# f407_board.net
KiCad netlist of a schematic drawn in Altium Designer
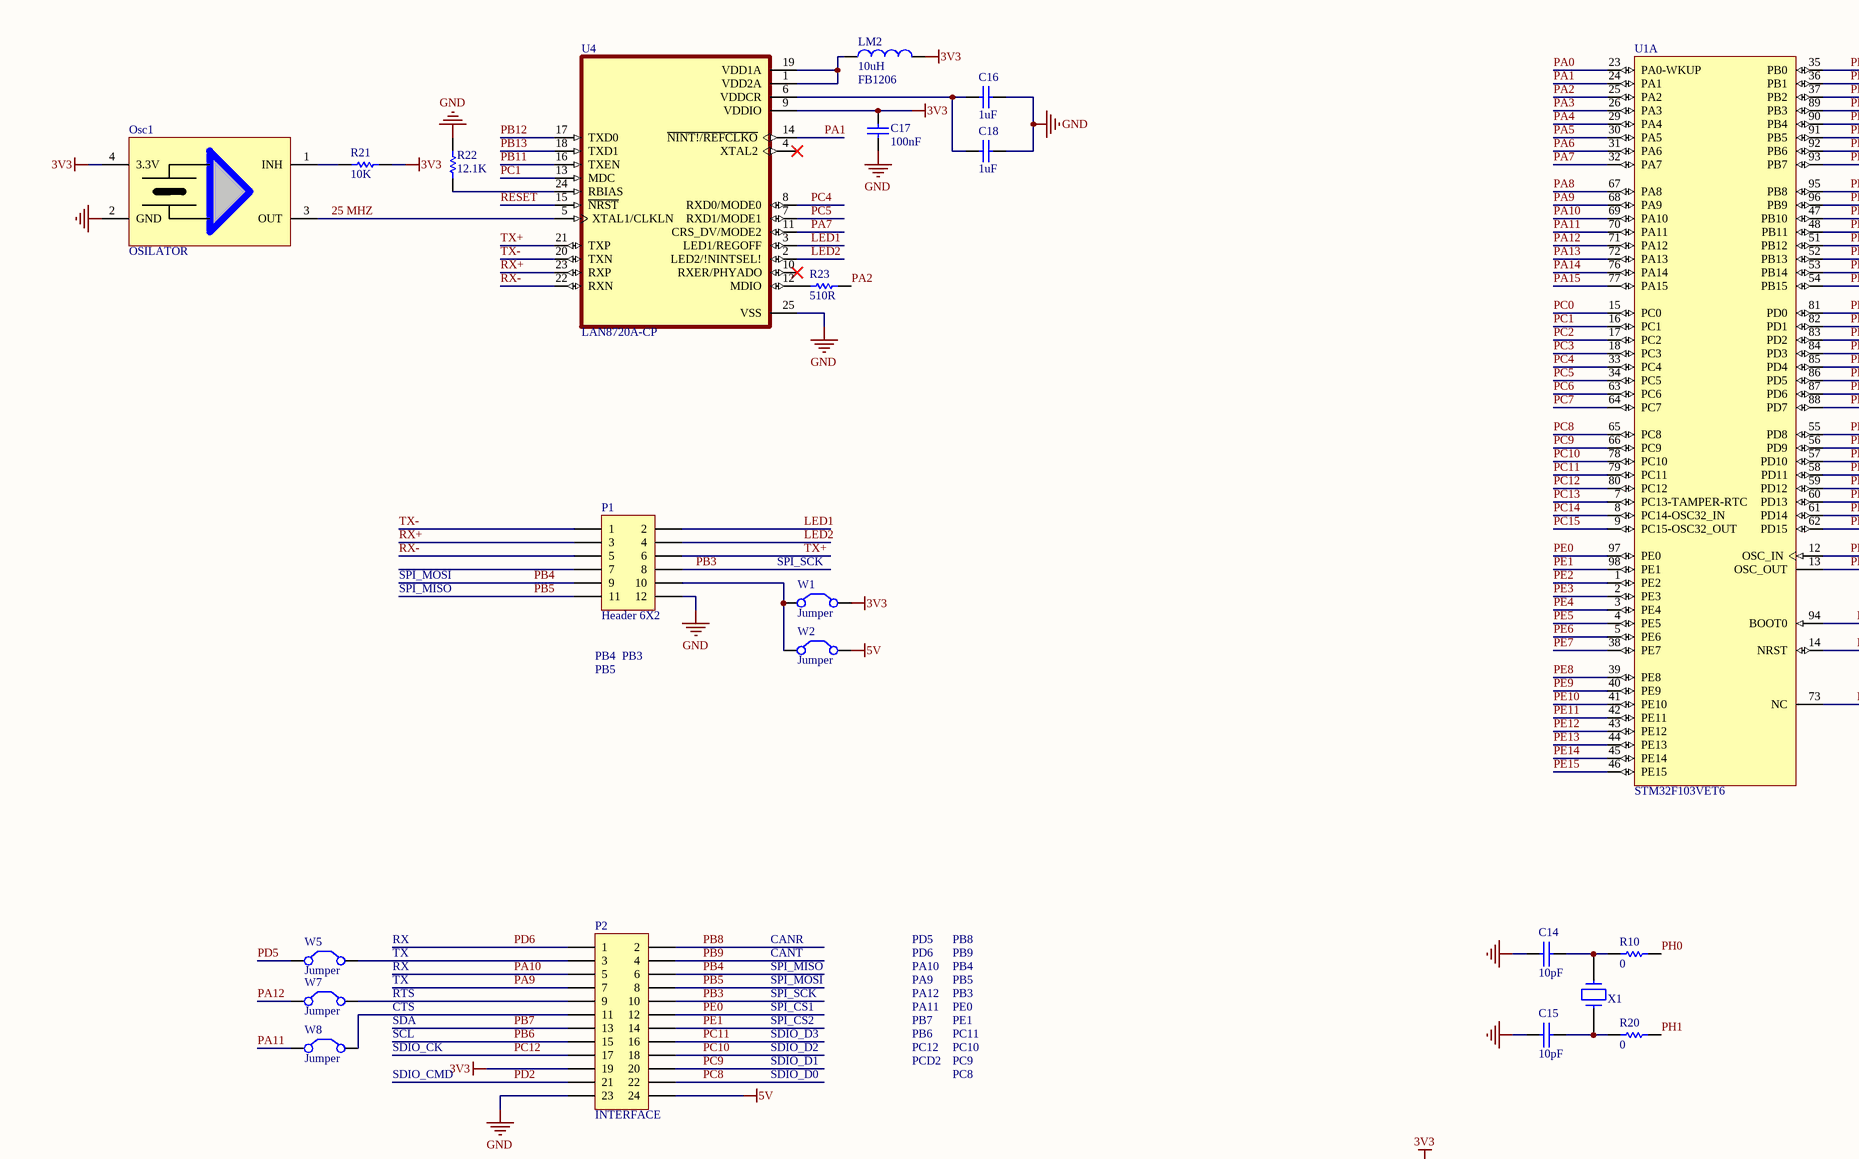
[diagram p0: f407 board.SchDoc, top left]
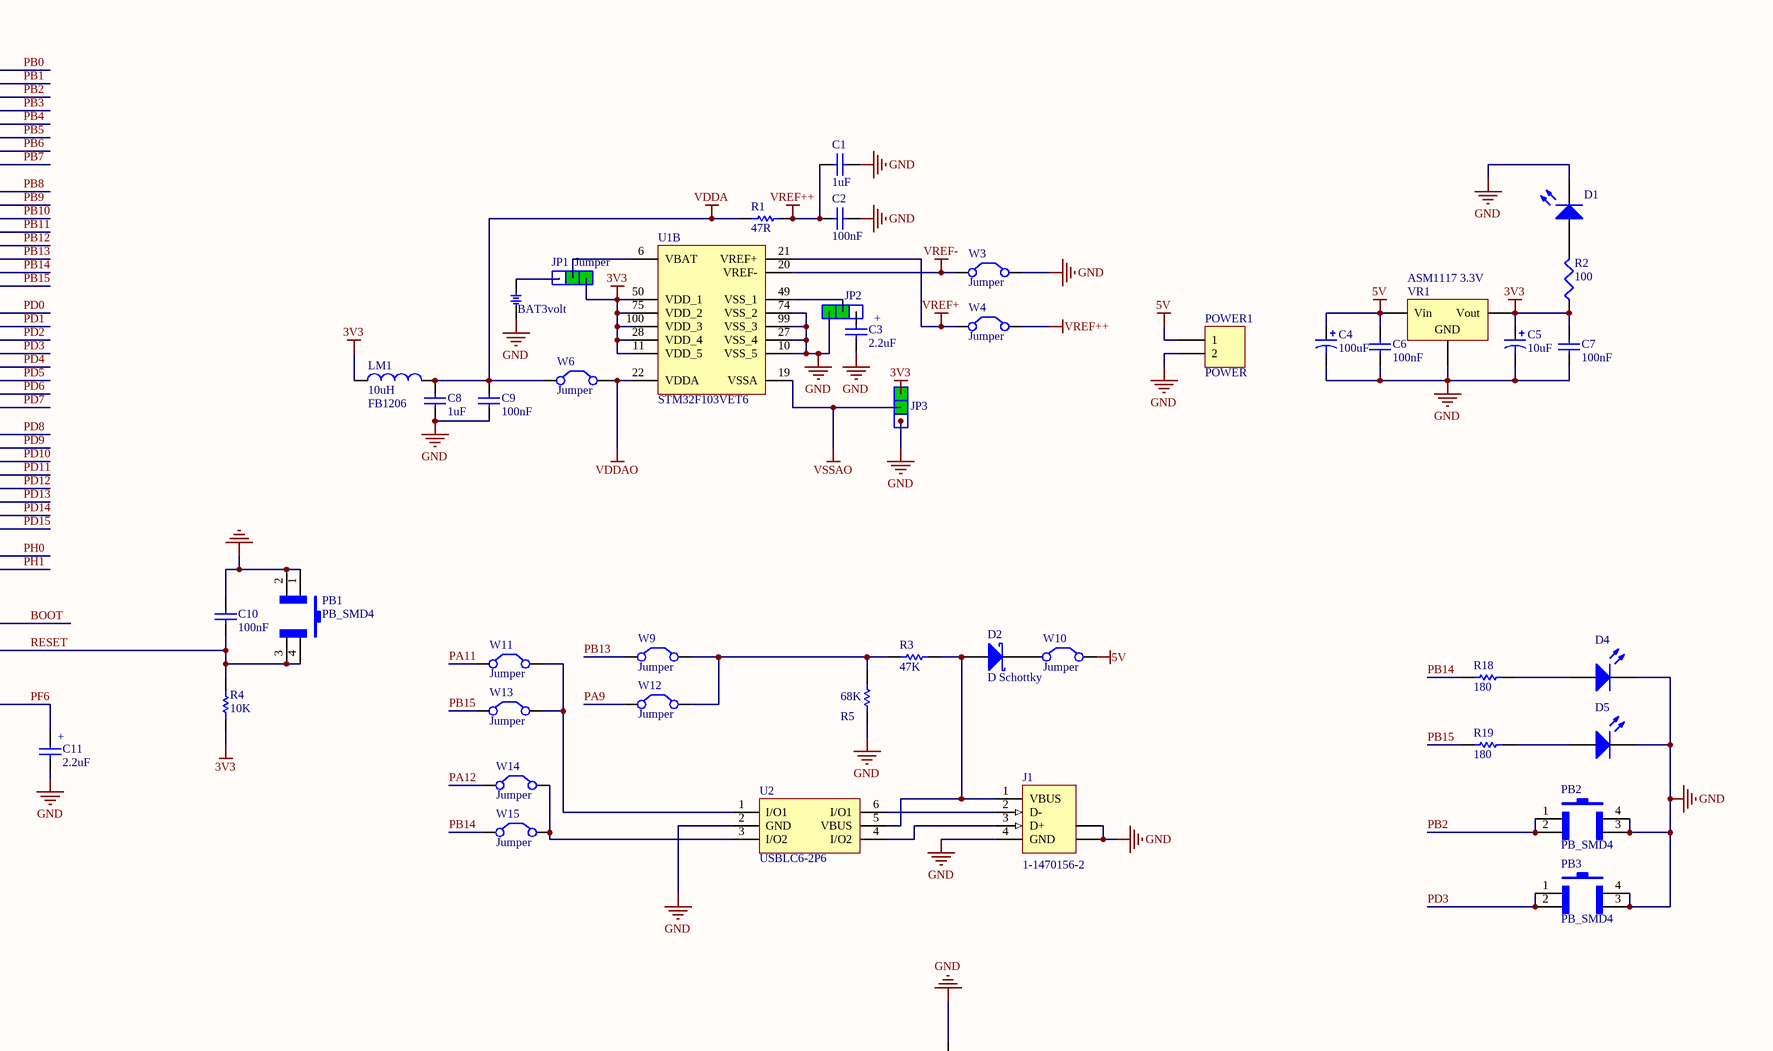
[diagram p1: f407 board.SchDoc, top right]
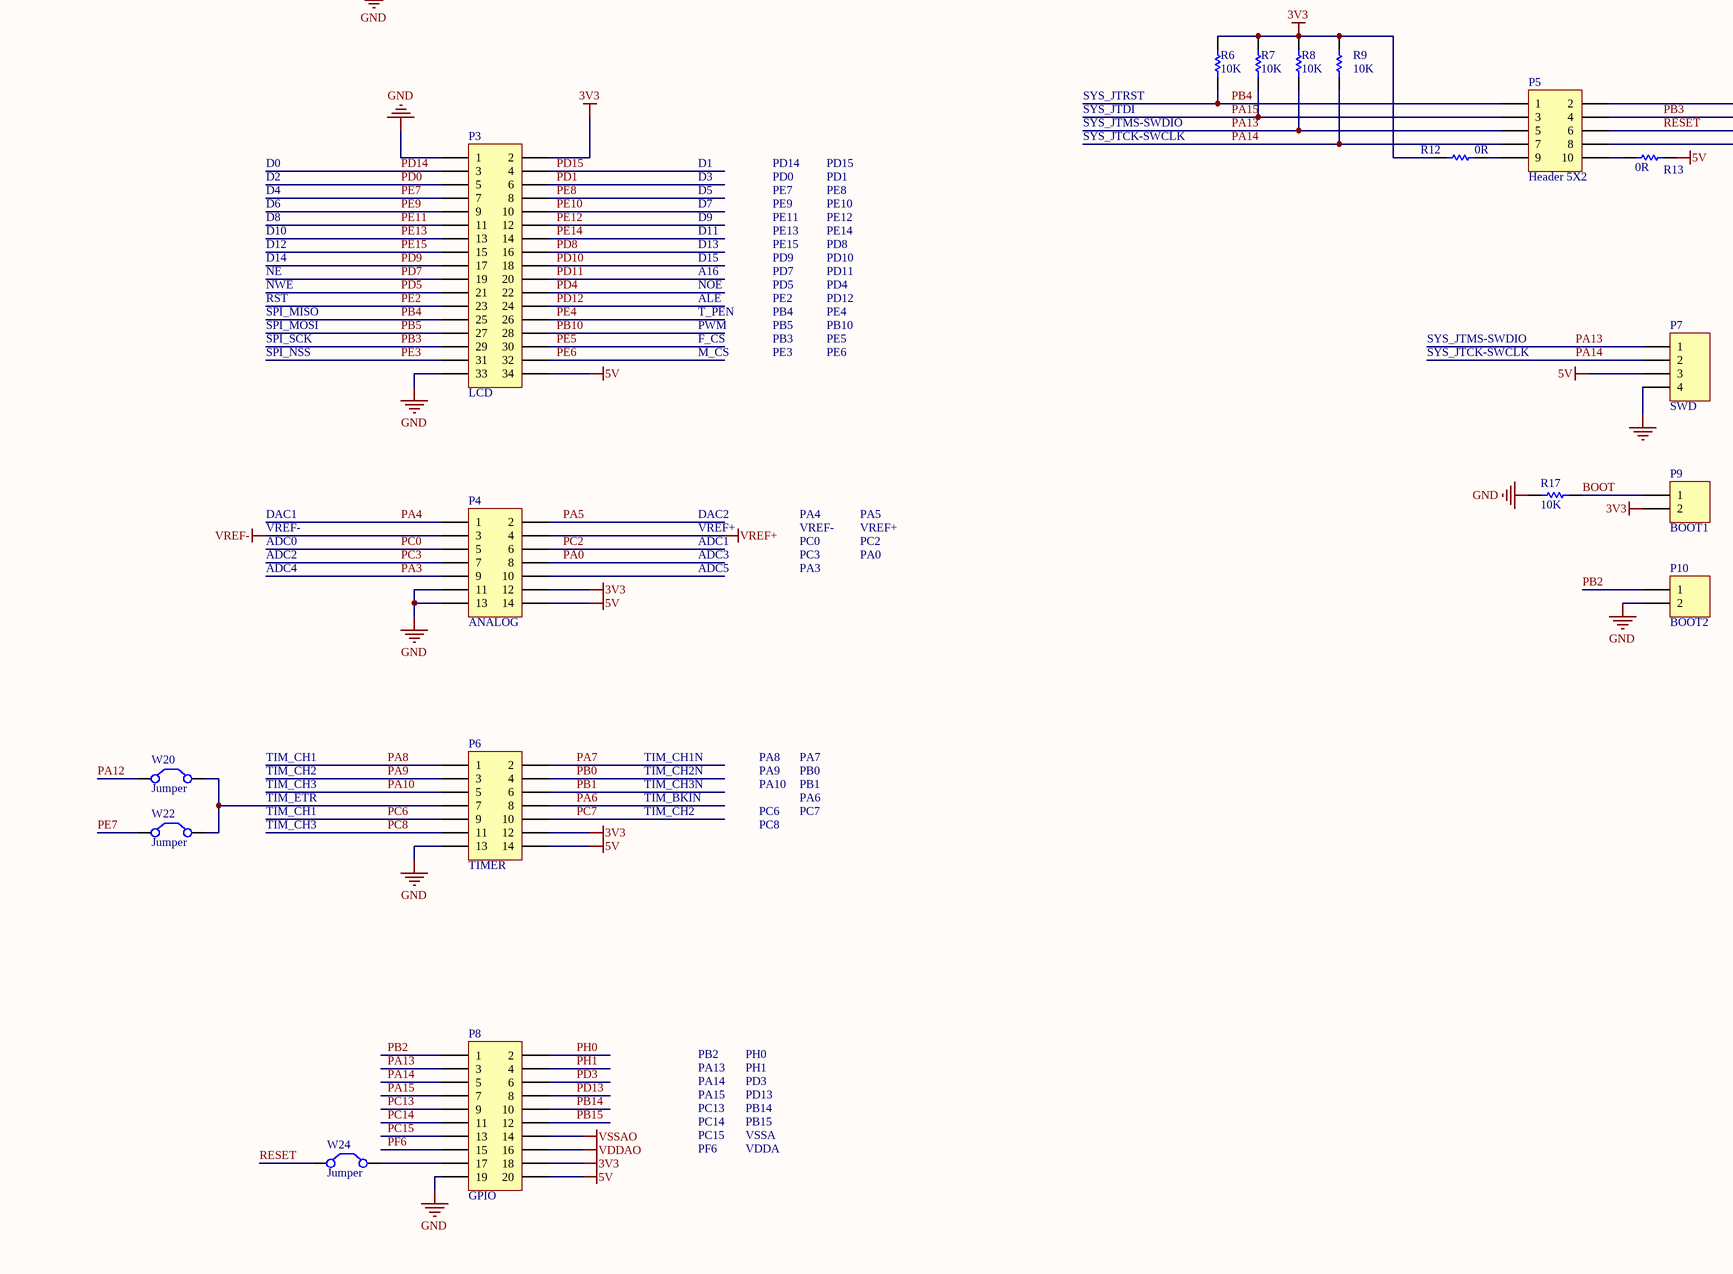
[diagram p2: f407 board.SchDoc, bottom left]
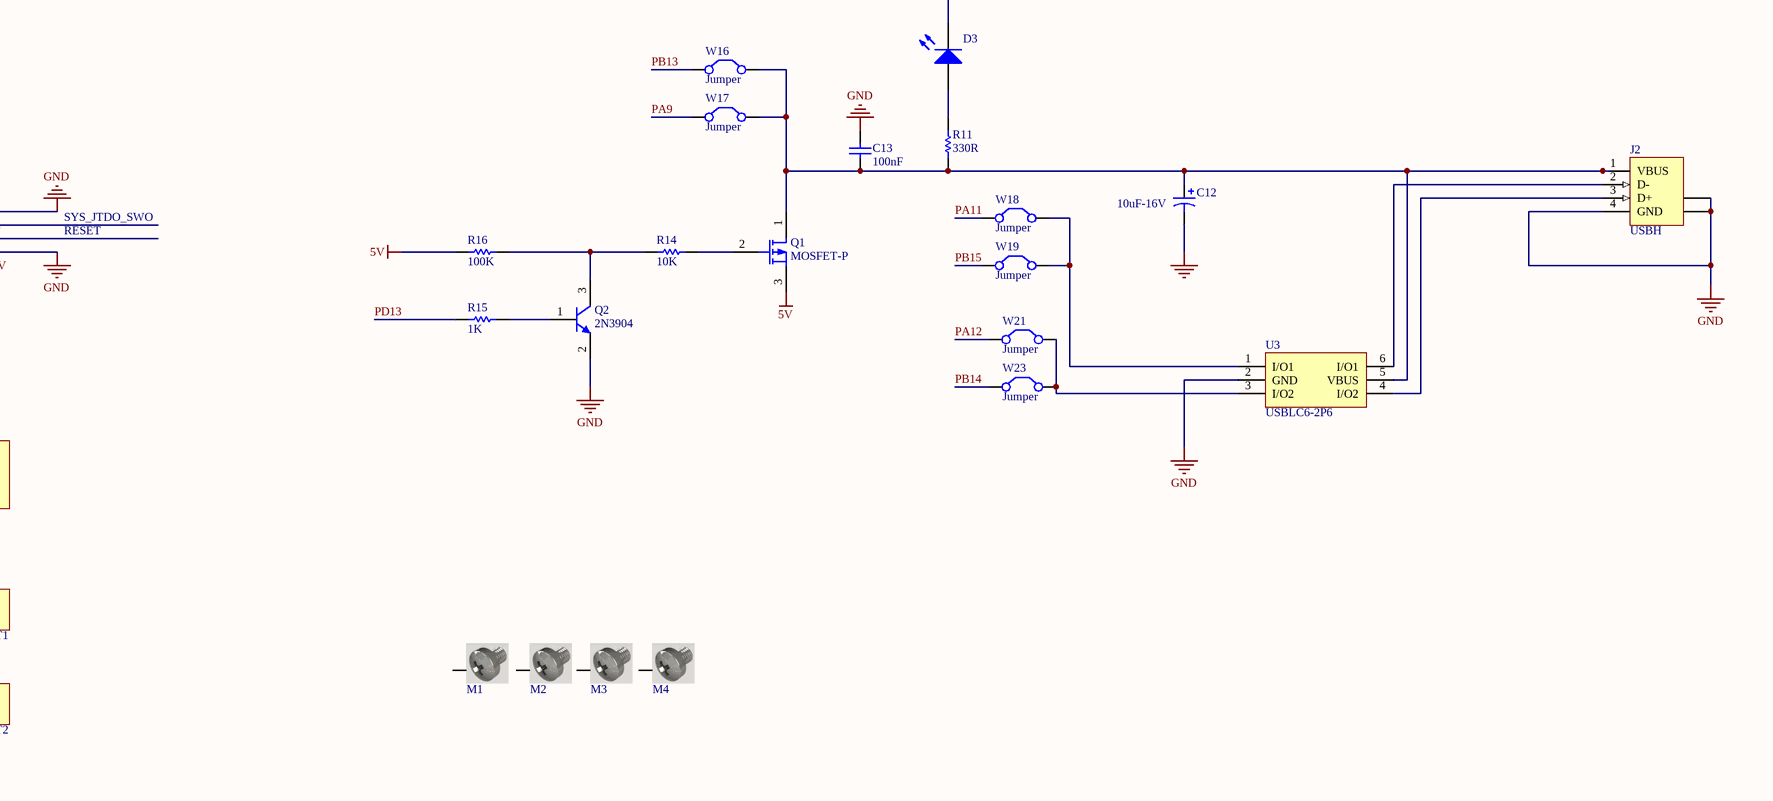
[diagram p3: f407 board.SchDoc, bottom right]

(export (version "E")
  (design (tool "Eeschema 10.0.6"))
  (components
    (comp (ref "BT1")
      (value "BAT3volt")
      (footprint "BTH1220")
      (description "BATTERY HOLDER, CR1220/CR2032")
      (libsource (lib "battery") (part "BATH_CR1220_CR2032"))
    )
    (comp (ref "C1")
      (value "1uF")
      (footprint "0805")
      (description "CAP 1206")
      (fields (field (name "DESIGNER") "Abbas Basereh"))
      (libsource (lib "2017AbbasBasereh9365731239 -ver1") (part "CAP SMD 1206"))
    )
    (comp (ref "C2")
      (value "100nF")
      (footprint "0805")
      (description "CAP 1206")
      (fields (field (name "DESIGNER") "Abbas Basereh"))
      (libsource (lib "2017AbbasBasereh9365731239 -ver1") (part "CAP SMD 1206"))
    )
    (comp (ref "C3")
      (value "2.2uF")
      (footprint "0805")
      (description "CAP 1206")
      (fields (field (name "DESIGNER") "Abbas Basereh"))
      (libsource (lib "2017AbbasBasereh9365731239 -ver1") (part "CAP SMD 1206"))
    )
    (comp (ref "C4")
      (value "100uF")
      (footprint "CAP470")
      (description "Polarized Capacitor (Radial)")
      (fields (field (name "Comment") "100uf") (field (name "PUBLISHER") "Altium Limited"))
      (libsource (lib "Miscellaneous Devices") (part "Cap Pol1"))
    )
    (comp (ref "C5")
      (value "10uF")
      (footprint "CAP10")
      (description "Polarized Capacitor (Radial)")
      (fields (field (name "Comment") "10uf") (field (name "PUBLISHER") "Altium Limited"))
      (libsource (lib "Miscellaneous Devices") (part "Cap Pol1"))
    )
    (comp (ref "C6")
      (value "100nF")
      (footprint "0805")
      (description "Capacitor (Semiconductor SIM Model)")
      (fields (field (name "PUBLISHER") "Altium Limited"))
      (libsource (lib "Miscellaneous Devices") (part "Cap Semi"))
    )
    (comp (ref "C7")
      (value "100nF")
      (footprint "0805")
      (description "Capacitor (Semiconductor SIM Model)")
      (fields (field (name "PUBLISHER") "Altium Limited"))
      (libsource (lib "Miscellaneous Devices") (part "Cap Semi"))
    )
    (comp (ref "C8")
      (value "1uF")
      (footprint "0805")
      (description "CAP 1206")
      (fields (field (name "DESIGNER") "Abbas Basereh"))
      (libsource (lib "2017AbbasBasereh9365731239 -ver1") (part "CAP SMD 1206"))
    )
    (comp (ref "C9")
      (value "100nF")
      (footprint "0805")
      (description "CAP 1206")
      (fields (field (name "DESIGNER") "Abbas Basereh"))
      (libsource (lib "2017AbbasBasereh9365731239 -ver1") (part "CAP SMD 1206"))
    )
    (comp (ref "C10")
      (value "100nF")
      (footprint "0805")
      (description "Capacitor")
      (fields (field (name "PUBLISHER") "Altium Limited"))
      (libsource (lib "Miscellaneous Devices") (part "CAP"))
    )
    (comp (ref "C11")
      (value "2.2uF")
      (footprint "0805")
      (description "CAP 1206")
      (fields (field (name "DESIGNER") "Abbas Basereh"))
      (libsource (lib "2017AbbasBasereh9365731239 -ver1") (part "CAP SMD 1206"))
    )
    (comp (ref "C12")
      (value "10uF-16V")
      (footprint "cap10")
      (description "Polarized Capacitor")
      (libsource (lib "mahdidadashi") (part "3-CAP-POL"))
    )
    (comp (ref "C13")
      (value "100nF")
      (footprint "0805")
      (description "Capacitor (Semiconductor SIM Model)")
      (fields (field (name "Comment") "10uf") (field (name "PUBLISHER") "Altium Limited"))
      (libsource (lib "Miscellaneous Devices") (part "Cap Semi"))
    )
    (comp (ref "C14")
      (value "10pF")
      (footprint "0805")
      (description "Capacitor")
      (libsource (lib "*") (part "CAP"))
    )
    (comp (ref "C15")
      (value "10pF")
      (footprint "0805")
      (description "Capacitor")
      (libsource (lib "*") (part "CAP"))
    )
    (comp (ref "C16")
      (value "1uF")
      (footprint "0805")
      (description "CAP 1206")
      (fields (field (name "DESIGNER") "Abbas Basereh"))
      (libsource (lib "2017AbbasBasereh9365731239 -ver1") (part "CAP SMD 1206"))
    )
    (comp (ref "C17")
      (value "100nF")
      (footprint "0805")
      (description "CAP 1206")
      (fields (field (name "DESIGNER") "Abbas Basereh"))
      (libsource (lib "2017AbbasBasereh9365731239 -ver1") (part "CAP SMD 1206"))
    )
    (comp (ref "C18")
      (value "1uF")
      (footprint "0805")
      (description "CAP 1206")
      (fields (field (name "DESIGNER") "Abbas Basereh"))
      (libsource (lib "2017AbbasBasereh9365731239 -ver1") (part "CAP SMD 1206"))
    )
    (comp (ref "D1")
      (value "LED0")
      (footprint "LED_0805")
      (description "Typical INFRARED GaAs LED")
      (fields (field (name "PUBLISHER") "Altium Limited"))
      (libsource (lib "Miscellaneous Devices") (part "LED0"))
    )
    (comp (ref "D2")
      (value "D Schottky")
      (footprint "SOD80, LL-34")
      (description "Schottky Diode")
      (fields (field (name "PUBLISHER") "Altium Limited"))
      (libsource (lib "Miscellaneous Devices") (part "D Schottky"))
    )
    (comp (ref "D3")
      (value "LED0")
      (footprint "LED_0805")
      (description "Typical INFRARED GaAs LED")
      (fields (field (name "PUBLISHER") "Altium Limited"))
      (libsource (lib "Miscellaneous Devices") (part "LED0"))
    )
    (comp (ref "D4")
      (value "LED0")
      (footprint "LED_0805")
      (description "Typical INFRARED GaAs LED")
      (fields (field (name "PUBLISHER") "Altium Limited"))
      (libsource (lib "Miscellaneous Devices") (part "LED0"))
    )
    (comp (ref "D5")
      (value "LED0")
      (footprint "LED_0805")
      (description "Typical INFRARED GaAs LED")
      (fields (field (name "PUBLISHER") "Altium Limited"))
      (libsource (lib "Miscellaneous Devices") (part "LED0"))
    )
    (comp (ref "J1")
      (value "1-1470156-2")
      (footprint "440247")
      (description "USB 1.1, Right Angle, Thru-Hole, B Type, Receptacle, 4 Position, Black")
      (fields (field (name "PUBLISHER") "Altium Limited"))
      (libsource (lib "AMP Serial Bus USB") (part "1-1470156-2"))
    )
    (comp (ref "J2")
      (value "USBH")
      (footprint "787761")
      (description "USB 1.1, Right Angle, Thru-Hole, A Type, Receptacle, 4 Position, Natural")
      (fields (field (name "PUBLISHER") "Altium Limited"))
      (libsource (lib "AMP Serial Bus USB") (part "787761-3"))
    )
    (comp (ref "JP1")
      (value "Jumper")
      (footprint "JT3")
      (description "Jumper Selector")
      (libsource (lib "Electrovolt Lib") (part "Jumper Selector"))
    )
    (comp (ref "JP2")
      (value "Jumper")
      (footprint "JT3")
      (description "Jumper Selector")
      (libsource (lib "") (part "Jumper Selector_1"))
    )
    (comp (ref "JP3")
      (value "Jumper")
      (footprint "JT3")
      (description "Jumper Selector")
      (libsource (lib "") (part "Jumper Selector_2"))
    )
    (comp (ref "LM1")
      (value "10uH")
      (footprint "0805")
      (description "Inductor")
      (fields (field (name "ALTIUM_VALUE") "FB1206") (field (name "PUBLISHER") "Altium Limited"))
      (libsource (lib "2017AbbasBasereh9365731239 -ver1") (part "L SMA 0.25W"))
    )
    (comp (ref "LM2")
      (value "10uH")
      (footprint "0805")
      (description "Inductor")
      (fields (field (name "ALTIUM_VALUE") "FB1206") (field (name "PUBLISHER") "Altium Limited"))
      (libsource (lib "2017AbbasBasereh9365731239 -ver1") (part "L SMA 0.25W"))
    )
    (comp (ref "M1")
      (value "Screw3mm")
      (footprint "Board Screw 3mm")
      (description "Board Screw With Spacer 3mm")
      (fields (field (name "DESIGNER") "Abbas Basereh"))
      (libsource (lib "2017AbbasBasereh9365731239 -ver1") (part "Board Screw 3mm"))
    )
    (comp (ref "M2")
      (value "Screw3mm")
      (footprint "Board Screw 3mm")
      (description "Board Screw With Spacer 3mm")
      (fields (field (name "DESIGNER") "Abbas Basereh"))
      (libsource (lib "2017AbbasBasereh9365731239 -ver1") (part "Board Screw 3mm"))
    )
    (comp (ref "M3")
      (value "Screw3mm")
      (footprint "Board Screw 3mm")
      (description "Board Screw With Spacer 3mm")
      (fields (field (name "DESIGNER") "Abbas Basereh"))
      (libsource (lib "2017AbbasBasereh9365731239 -ver1") (part "Board Screw 3mm"))
    )
    (comp (ref "M4")
      (value "Screw3mm")
      (footprint "Board Screw 3mm")
      (description "Board Screw With Spacer 3mm")
      (fields (field (name "DESIGNER") "Abbas Basereh"))
      (libsource (lib "2017AbbasBasereh9365731239 -ver1") (part "Board Screw 3mm"))
    )
    (comp (ref "Osc1")
      (value "OSILATOR")
      (footprint "XTAL_5X7")
      (libsource (lib "New Lib") (part "OSILATOR"))
    )
    (comp (ref "P1")
      (value "Header 6X2")
      (footprint "HDR2X6")
      (description "Header, 6-Pin, Dual row")
      (fields (field (name "PUBLISHER") "Altium Limited"))
      (libsource (lib "Miscellaneous Connectors") (part "Header 6X2"))
    )
    (comp (ref "P2")
      (value "INTERFACE")
      (footprint "HDR2X12")
      (description "Header, 12-Pin, Dual row")
      (fields (field (name "PUBLISHER") "Altium Limited"))
      (libsource (lib "Miscellaneous Connectors") (part "Header 12X2"))
    )
    (comp (ref "P3")
      (value "LCD")
      (footprint "HDR2X17")
      (description "Header, 17-Pin, Dual row")
      (fields (field (name "PUBLISHER") "Altium Limited"))
      (libsource (lib "Miscellaneous Connectors") (part "Header 17X2"))
    )
    (comp (ref "P4")
      (value "ANALOG")
      (footprint "HDR2X7")
      (description "Header, 7-Pin, Dual row")
      (fields (field (name "PUBLISHER") "Altium Limited"))
      (libsource (lib "Miscellaneous Connectors") (part "Header 7X2"))
    )
    (comp (ref "P5")
      (value "Header 5X2")
      (footprint "HDR2X5")
      (description "Header, 5-Pin, Dual row")
      (fields (field (name "PUBLISHER") "Altium Limited"))
      (libsource (lib "Miscellaneous Connectors") (part "Header 5X2"))
    )
    (comp (ref "P6")
      (value "TIMER")
      (footprint "HDR2X7")
      (description "Header, 7-Pin, Dual row")
      (fields (field (name "PUBLISHER") "Altium Limited"))
      (libsource (lib "Miscellaneous Connectors") (part "Header 7X2"))
    )
    (comp (ref "P7")
      (value "SWD")
      (footprint "HDR1X4")
      (description "Header, 4-Pin")
      (fields (field (name "PUBLISHER") "Altium Limited"))
      (libsource (lib "Miscellaneous Connectors") (part "Header 4"))
    )
    (comp (ref "P8")
      (value "GPIO")
      (footprint "HDR2X10")
      (description "Header, 10-Pin, Dual row")
      (fields (field (name "PUBLISHER") "Altium Limited"))
      (libsource (lib "Miscellaneous Connectors") (part "Header 10X2"))
    )
    (comp (ref "P9")
      (value "BOOT1")
      (footprint "HDR1X2")
      (description "Header, 2-Pin")
      (fields (field (name "PUBLISHER") "Altium Limited"))
      (libsource (lib "Miscellaneous Connectors") (part "Header 2"))
    )
    (comp (ref "P10")
      (value "BOOT2")
      (footprint "HDR1X2")
      (description "Header, 2-Pin")
      (fields (field (name "PUBLISHER") "Altium Limited"))
      (libsource (lib "Miscellaneous Connectors") (part "Header 2"))
    )
    (comp (ref "PB1")
      (value "PB_SMD4")
      (footprint "PB_SMD4")
      (fields (field (name "PART_NUMBER") "SW-PB-AX-SMD4"))
      (libsource (lib "SCHLib") (part "PB_SMD4"))
    )
    (comp (ref "PB2")
      (value "PB_SMD4")
      (footprint "PB_SMD4")
      (fields (field (name "PART_NUMBER") "SW-PB-AX-SMD4"))
      (libsource (lib "") (part "PB_SMD4_1"))
    )
    (comp (ref "PB3")
      (value "PB_SMD4")
      (footprint "PB_SMD4")
      (fields (field (name "PART_NUMBER") "SW-PB-AX-SMD4"))
      (libsource (lib "") (part "PB_SMD4_1"))
    )
    (comp (ref "POWER1")
      (value "POWER")
      (footprint "power jack")
      (description "Header, 2-Pin, Right Angle")
      (fields (field (name "PUBLISHER") "Altium Limited"))
      (libsource (lib "Miscellaneous Connectors") (part "Header 2H"))
    )
    (comp (ref "Q1")
      (value "MOSFET-P")
      (footprint "SUPER SOT_3")
      (description "P-Channel MOSFET")
      (fields (field (name "PUBLISHER") "Altium Limited"))
      (libsource (lib "Miscellaneous Devices") (part "MOSFET-P"))
    )
    (comp (ref "Q2")
      (value "2N3904")
      (footprint "SOT-23")
      (description "NPN General Purpose Amplifier")
      (fields (field (name "PUBLISHER") "Altium Limited"))
      (libsource (lib "Miscellaneous Devices") (part "2N3904"))
    )
    (comp (ref "R1")
      (value "47R")
      (footprint "0805")
      (description "RES 1206")
      (fields (field (name "DESIGNER") "Abbas Basereh"))
      (libsource (lib "2017AbbasBasereh9365731239 -ver1") (part "RES 1206 0.25W"))
    )
    (comp (ref "R2")
      (value "100")
      (footprint "0805")
      (description "Resistor")
      (fields (field (name "PUBLISHER") "Altium Limited"))
      (libsource (lib "Miscellaneous Devices") (part "Res3"))
    )
    (comp (ref "R3")
      (value "47K")
      (footprint "0805")
      (description "Resistor")
      (fields (field (name "PUBLISHER") "Altium Limited"))
      (libsource (lib "") (part "Res1_1"))
    )
    (comp (ref "R4")
      (value "10K")
      (footprint "0805")
      (description "Resistor")
      (fields (field (name "PUBLISHER") "Altium Limited"))
      (libsource (lib "Miscellaneous Devices") (part "res1"))
    )
    (comp (ref "R5")
      (value "68K")
      (footprint "0805")
      (description "Resistor")
      (fields (field (name "PUBLISHER") "Altium Limited"))
      (libsource (lib "") (part "Res1_1"))
    )
    (comp (ref "R6")
      (value "10K")
      (footprint "0805")
      (description "Resistor")
      (fields (field (name "PUBLISHER") "Altium Limited"))
      (libsource (lib "Miscellaneous Devices") (part "Res1"))
    )
    (comp (ref "R7")
      (value "10K")
      (footprint "0805")
      (description "Resistor")
      (fields (field (name "PUBLISHER") "Altium Limited"))
      (libsource (lib "Miscellaneous Devices") (part "Res1"))
    )
    (comp (ref "R8")
      (value "10K")
      (footprint "0805")
      (description "Resistor")
      (fields (field (name "PUBLISHER") "Altium Limited"))
      (libsource (lib "Miscellaneous Devices") (part "Res1"))
    )
    (comp (ref "R9")
      (value "10K")
      (footprint "0805")
      (description "Resistor")
      (fields (field (name "PUBLISHER") "Altium Limited"))
      (libsource (lib "Miscellaneous Devices") (part "Res1"))
    )
    (comp (ref "R10")
      (value "0")
      (footprint "0805")
      (description "Resistor")
      (fields (field (name "PUBLISHER") "Altium Limited"))
      (libsource (lib "Miscellaneous Devices") (part "Res1"))
    )
    (comp (ref "R11")
      (value "330R")
      (footprint "0805")
      (description "Resistor")
      (fields (field (name "PUBLISHER") "Altium Limited"))
      (libsource (lib "") (part "Res1_1"))
    )
    (comp (ref "R12")
      (value "0R")
      (footprint "0805")
      (description "Resistor")
      (fields (field (name "PUBLISHER") "Altium Limited"))
      (libsource (lib "Miscellaneous Devices") (part "Res1"))
    )
    (comp (ref "R13")
      (value "0R")
      (footprint "0805")
      (description "Resistor")
      (fields (field (name "PUBLISHER") "Altium Limited"))
      (libsource (lib "Miscellaneous Devices") (part "Res1"))
    )
    (comp (ref "R14")
      (value "10K")
      (footprint "0805")
      (description "Resistor")
      (fields (field (name "PUBLISHER") "Altium Limited"))
      (libsource (lib "") (part "Res1_1"))
    )
    (comp (ref "R15")
      (value "1K")
      (footprint "0805")
      (description "Resistor")
      (fields (field (name "PUBLISHER") "Altium Limited"))
      (libsource (lib "") (part "Res1_1"))
    )
    (comp (ref "R16")
      (value "100K")
      (footprint "0805")
      (description "Resistor")
      (fields (field (name "PUBLISHER") "Altium Limited"))
      (libsource (lib "") (part "Res1_1"))
    )
    (comp (ref "R17")
      (value "10K")
      (footprint "0805")
      (description "Resistor")
      (fields (field (name "PUBLISHER") "Altium Limited"))
      (libsource (lib "Miscellaneous Devices") (part "Res1"))
    )
    (comp (ref "R18")
      (value "180")
      (footprint "0805")
      (description "Resistor")
      (fields (field (name "PUBLISHER") "Altium Limited"))
      (libsource (lib "Miscellaneous Devices") (part "Res1"))
    )
    (comp (ref "R19")
      (value "180")
      (footprint "0805")
      (description "Resistor")
      (fields (field (name "PUBLISHER") "Altium Limited"))
      (libsource (lib "Miscellaneous Devices") (part "Res1"))
    )
    (comp (ref "R20")
      (value "0")
      (description "Resistor")
      (fields (field (name "PUBLISHER") "Altium Limited"))
      (libsource (lib "Miscellaneous Devices") (part "Res1"))
    )
    (comp (ref "R21")
      (value "10K")
      (footprint "0805")
      (description "Resistor")
      (fields (field (name "PUBLISHER") "Altium Limited"))
      (libsource (lib "") (part "Res1_1"))
    )
    (comp (ref "R22")
      (value "12.1K")
      (footprint "0805")
      (description "Resistor")
      (fields (field (name "PUBLISHER") "Altium Limited"))
      (libsource (lib "") (part "Res1_1"))
    )
    (comp (ref "R23")
      (value "510R")
      (footprint "0805")
      (description "Resistor")
      (fields (field (name "PUBLISHER") "Altium Limited"))
      (libsource (lib "") (part "Res1_1"))
    )
    (comp (ref "U1")
      (value "STM32F103VET6")
      (footprint "LQFP100")
      (libsource (lib "STMicroelectronics STM32 F1") (part "STM32F103VET6"))
    )
    (comp (ref "U2")
      (value "USBLC6-2P6")
      (footprint "SOT23-6")
      (libsource (lib "mahdidadashi") (part "USBLC6-2P6"))
    )
    (comp (ref "U3")
      (value "USBLC6-2P6")
      (footprint "SOT23-6")
      (libsource (lib "mahdidadashi") (part "USBLC6-2P6"))
    )
    (comp (ref "U4")
      (value "LAN8720A-CP")
      (footprint "QFN50P400X400X100-25N")
      (description "2/2 Transceiver Full RMII 24-QFN-EP _4x4_")
      (fields (field (name "MF") "Microchip"))
      (libsource (lib "LAN8720A-CP") (part "LAN8720A-CP"))
    )
    (comp (ref "VR1")
      (value "ASM1117 3.3V")
      (footprint "Regolator")
      (description "Voltage Regulator")
      (fields (field (name "PUBLISHER") "Altium Limited"))
      (libsource (lib "Miscellaneous Devices") (part "Volt Reg_1"))
    )
    (comp (ref "W1")
      (value "Jumper")
      (footprint "JP2_SMD")
      (description "Jumper Wire")
      (fields (field (name "PUBLISHER") "Altium Limited"))
      (libsource (lib "Miscellaneous Devices") (part "Jumper"))
    )
    (comp (ref "W2")
      (value "Jumper")
      (footprint "JP2_SMD")
      (description "Jumper Wire")
      (fields (field (name "PUBLISHER") "Altium Limited"))
      (libsource (lib "Miscellaneous Devices") (part "Jumper"))
    )
    (comp (ref "W3")
      (value "Jumper")
      (footprint "JP2_SMD")
      (description "Jumper Wire")
      (fields (field (name "PUBLISHER") "Altium Limited"))
      (libsource (lib "Miscellaneous Devices") (part "Jumper"))
    )
    (comp (ref "W4")
      (value "Jumper")
      (footprint "JP2_SMD")
      (description "Jumper Wire")
      (fields (field (name "PUBLISHER") "Altium Limited"))
      (libsource (lib "Miscellaneous Devices") (part "Jumper"))
    )
    (comp (ref "W5")
      (value "Jumper")
      (footprint "JP2_SMD")
      (description "Jumper Wire")
      (fields (field (name "PUBLISHER") "Altium Limited"))
      (libsource (lib "Miscellaneous Devices") (part "Jumper"))
    )
    (comp (ref "W6")
      (value "Jumper")
      (footprint "JP2_SMD")
      (description "Jumper Wire")
      (fields (field (name "PUBLISHER") "Altium Limited"))
      (libsource (lib "Miscellaneous Devices") (part "Jumper"))
    )
    (comp (ref "W7")
      (value "Jumper")
      (footprint "JP2_SMD")
      (description "Jumper Wire")
      (fields (field (name "PUBLISHER") "Altium Limited"))
      (libsource (lib "Miscellaneous Devices") (part "Jumper"))
    )
    (comp (ref "W8")
      (value "Jumper")
      (footprint "JP2_SMD")
      (description "Jumper Wire")
      (fields (field (name "PUBLISHER") "Altium Limited"))
      (libsource (lib "Miscellaneous Devices") (part "Jumper"))
    )
    (comp (ref "W9")
      (value "Jumper")
      (footprint "JP2_SMD")
      (description "Jumper Wire")
      (fields (field (name "PUBLISHER") "Altium Limited"))
      (libsource (lib "Miscellaneous Devices") (part "Jumper"))
    )
    (comp (ref "W10")
      (value "Jumper")
      (footprint "JP2_SMD")
      (description "Jumper Wire")
      (fields (field (name "PUBLISHER") "Altium Limited"))
      (libsource (lib "Miscellaneous Devices") (part "Jumper"))
    )
    (comp (ref "W11")
      (value "Jumper")
      (footprint "JP2_SMD")
      (description "Jumper Wire")
      (fields (field (name "PUBLISHER") "Altium Limited"))
      (libsource (lib "Miscellaneous Devices") (part "Jumper"))
    )
    (comp (ref "W12")
      (value "Jumper")
      (footprint "JP2_SMD")
      (description "Jumper Wire")
      (fields (field (name "PUBLISHER") "Altium Limited"))
      (libsource (lib "Miscellaneous Devices") (part "Jumper"))
    )
    (comp (ref "W13")
      (value "Jumper")
      (footprint "JP2_SMD")
      (description "Jumper Wire")
      (fields (field (name "PUBLISHER") "Altium Limited"))
      (libsource (lib "Miscellaneous Devices") (part "Jumper"))
    )
    (comp (ref "W14")
      (value "Jumper")
      (footprint "JP2_SMD")
      (description "Jumper Wire")
      (fields (field (name "PUBLISHER") "Altium Limited"))
      (libsource (lib "Miscellaneous Devices") (part "Jumper"))
    )
    (comp (ref "W15")
      (value "Jumper")
      (footprint "JP2_SMD")
      (description "Jumper Wire")
      (fields (field (name "PUBLISHER") "Altium Limited"))
      (libsource (lib "Miscellaneous Devices") (part "Jumper"))
    )
    (comp (ref "W16")
      (value "Jumper")
      (footprint "JP2_SMD")
      (description "Jumper Wire")
      (fields (field (name "PUBLISHER") "Altium Limited"))
      (libsource (lib "Miscellaneous Devices") (part "Jumper"))
    )
    (comp (ref "W17")
      (value "Jumper")
      (footprint "JP2_SMD")
      (description "Jumper Wire")
      (fields (field (name "PUBLISHER") "Altium Limited"))
      (libsource (lib "Miscellaneous Devices") (part "Jumper"))
    )
    (comp (ref "W18")
      (value "Jumper")
      (footprint "JP2_SMD")
      (description "Jumper Wire")
      (fields (field (name "PUBLISHER") "Altium Limited"))
      (libsource (lib "Miscellaneous Devices") (part "Jumper"))
    )
    (comp (ref "W19")
      (value "Jumper")
      (footprint "JP2_SMD")
      (description "Jumper Wire")
      (fields (field (name "PUBLISHER") "Altium Limited"))
      (libsource (lib "Miscellaneous Devices") (part "Jumper"))
    )
    (comp (ref "W20")
      (value "Jumper")
      (footprint "JP2_SMD")
      (description "Jumper Wire")
      (fields (field (name "PUBLISHER") "Altium Limited"))
      (libsource (lib "Miscellaneous Devices") (part "Jumper"))
    )
    (comp (ref "W21")
      (value "Jumper")
      (footprint "JP2_SMD")
      (description "Jumper Wire")
      (fields (field (name "PUBLISHER") "Altium Limited"))
      (libsource (lib "Miscellaneous Devices") (part "Jumper"))
    )
    (comp (ref "W22")
      (value "Jumper")
      (footprint "JP2_SMD")
      (description "Jumper Wire")
      (fields (field (name "PUBLISHER") "Altium Limited"))
      (libsource (lib "Miscellaneous Devices") (part "Jumper"))
    )
    (comp (ref "W23")
      (value "Jumper")
      (footprint "JP2_SMD")
      (description "Jumper Wire")
      (fields (field (name "PUBLISHER") "Altium Limited"))
      (libsource (lib "Miscellaneous Devices") (part "Jumper"))
    )
    (comp (ref "W24")
      (value "Jumper")
      (footprint "JP2_SMD")
      (description "Jumper Wire")
      (fields (field (name "PUBLISHER") "Altium Limited"))
      (libsource (lib "Miscellaneous Devices") (part "Jumper"))
    )
    (comp (ref "X1")
      (value "HC-49S-C16QSA-8M(jfvny)(with socket)")
      (footprint "XTAL_DIP")
      (description "Crystal")
      (libsource (lib "*") (part "CRYSTAL"))
    )
  )
  (nets
    (net (code "1") (name "/25 MHZ") (class "Default")
      (node (ref "Osc1") (pin "3") (pinfunction "OUT_3") (pintype "passive"))
      (node (ref "U4") (pin "5") (pinfunction "XTAL1/CLKLN_5") (pintype "input"))
    )
    (net (code "2") (name "/BOOT") (class "Default")
      (node (ref "P9") (pin "1") (pinfunction "1_1") (pintype "passive"))
      (node (ref "R17") (pin "1") (pinfunction "1_1") (pintype "passive"))
      (node (ref "U1") (pin "94") (pinfunction "BOOT0_94") (pintype "input"))
    )
    (net (code "3") (name "/LED1") (class "Default")
      (node (ref "P1") (pin "2") (pinfunction "2_2") (pintype "passive"))
      (node (ref "U4") (pin "3") (pinfunction "LED1/REGOFF_3") (pintype "bidirectional"))
    )
    (net (code "4") (name "/LED2") (class "Default")
      (node (ref "P1") (pin "4") (pinfunction "4_4") (pintype "passive"))
      (node (ref "U4") (pin "2") (pinfunction "LED2/!NINTSEL!_2") (pintype "bidirectional"))
    )
    (net (code "5") (name "/PA0") (class "Default")
      (node (ref "P4") (pin "8") (pinfunction "8_8") (pintype "passive"))
      (node (ref "U1") (pin "23") (pinfunction "PA0-WKUP_23") (pintype "bidirectional"))
    )
    (net (code "6") (name "/PA1") (class "Default")
      (node (ref "U1") (pin "24") (pinfunction "PA1_24") (pintype "bidirectional"))
      (node (ref "U4") (pin "14") (pinfunction "~{NINT!/REFCLKO}_14") (pintype "output"))
    )
    (net (code "7") (name "/PA2") (class "Default")
      (node (ref "R23") (pin "2") (pinfunction "2_2") (pintype "passive"))
      (node (ref "U1") (pin "25") (pinfunction "PA2_25") (pintype "bidirectional"))
    )
    (net (code "8") (name "/PA3") (class "Default")
      (node (ref "P4") (pin "9") (pinfunction "9_9") (pintype "passive"))
      (node (ref "U1") (pin "26") (pinfunction "PA3_26") (pintype "bidirectional"))
    )
    (net (code "9") (name "/PA4") (class "Default")
      (node (ref "P4") (pin "1") (pinfunction "1_1") (pintype "passive"))
      (node (ref "U1") (pin "29") (pinfunction "PA4_29") (pintype "bidirectional"))
    )
    (net (code "10") (name "/PA5") (class "Default")
      (node (ref "P4") (pin "2") (pinfunction "2_2") (pintype "passive"))
      (node (ref "U1") (pin "30") (pinfunction "PA5_30") (pintype "bidirectional"))
    )
    (net (code "11") (name "/PA6") (class "Default")
      (node (ref "P6") (pin "8") (pinfunction "8_8") (pintype "passive"))
      (node (ref "U1") (pin "31") (pinfunction "PA6_31") (pintype "bidirectional"))
    )
    (net (code "12") (name "/PA7") (class "Default")
      (node (ref "P6") (pin "2") (pinfunction "2_2") (pintype "passive"))
      (node (ref "U1") (pin "32") (pinfunction "PA7_32") (pintype "bidirectional"))
      (node (ref "U4") (pin "11") (pinfunction "CRS_DV/MODE2_11") (pintype "bidirectional"))
    )
    (net (code "13") (name "/PA8") (class "Default")
      (node (ref "P6") (pin "1") (pinfunction "1_1") (pintype "passive"))
      (node (ref "U1") (pin "67") (pinfunction "PA8_67") (pintype "bidirectional"))
    )
    (net (code "14") (name "/PA9") (class "Default")
      (node (ref "P2") (pin "7") (pinfunction "7_7") (pintype "passive"))
      (node (ref "P6") (pin "3") (pinfunction "3_3") (pintype "passive"))
      (node (ref "U1") (pin "68") (pinfunction "PA9_68") (pintype "bidirectional"))
      (node (ref "W12") (pin "1") (pinfunction "C1_1") (pintype "passive"))
      (node (ref "W17") (pin "1") (pinfunction "C1_1") (pintype "passive"))
    )
    (net (code "15") (name "/PA10") (class "Default")
      (node (ref "P2") (pin "5") (pinfunction "5_5") (pintype "passive"))
      (node (ref "P6") (pin "5") (pinfunction "5_5") (pintype "passive"))
      (node (ref "U1") (pin "69") (pinfunction "PA10_69") (pintype "bidirectional"))
    )
    (net (code "16") (name "/PA11") (class "Default")
      (node (ref "U1") (pin "70") (pinfunction "PA11_70") (pintype "bidirectional"))
      (node (ref "W11") (pin "1") (pinfunction "C1_1") (pintype "passive"))
      (node (ref "W18") (pin "1") (pinfunction "C1_1") (pintype "passive"))
      (node (ref "W8") (pin "1") (pinfunction "C1_1") (pintype "passive"))
    )
    (net (code "17") (name "/PA12") (class "Default")
      (node (ref "U1") (pin "71") (pinfunction "PA12_71") (pintype "bidirectional"))
      (node (ref "W14") (pin "1") (pinfunction "C1_1") (pintype "passive"))
      (node (ref "W20") (pin "1") (pinfunction "C1_1") (pintype "passive"))
      (node (ref "W21") (pin "1") (pinfunction "C1_1") (pintype "passive"))
      (node (ref "W7") (pin "1") (pinfunction "C1_1") (pintype "passive"))
    )
    (net (code "18") (name "/PA13") (class "Default")
      (node (ref "P5") (pin "5") (pinfunction "5_5") (pintype "passive"))
      (node (ref "P7") (pin "1") (pinfunction "1_1") (pintype "passive"))
      (node (ref "P8") (pin "3") (pinfunction "3_3") (pintype "passive"))
      (node (ref "R8") (pin "1") (pinfunction "1_1") (pintype "passive"))
      (node (ref "U1") (pin "72") (pinfunction "PA13_72") (pintype "bidirectional"))
    )
    (net (code "19") (name "/PA14") (class "Default")
      (node (ref "P5") (pin "7") (pinfunction "7_7") (pintype "passive"))
      (node (ref "P7") (pin "2") (pinfunction "2_2") (pintype "passive"))
      (node (ref "P8") (pin "5") (pinfunction "5_5") (pintype "passive"))
      (node (ref "R9") (pin "1") (pinfunction "1_1") (pintype "passive"))
      (node (ref "U1") (pin "76") (pinfunction "PA14_76") (pintype "bidirectional"))
    )
    (net (code "20") (name "/PA15") (class "Default")
      (node (ref "P5") (pin "3") (pinfunction "3_3") (pintype "passive"))
      (node (ref "P8") (pin "7") (pinfunction "7_7") (pintype "passive"))
      (node (ref "R7") (pin "1") (pinfunction "1_1") (pintype "passive"))
      (node (ref "U1") (pin "77") (pinfunction "PA15_77") (pintype "bidirectional"))
    )
    (net (code "21") (name "/PB0") (class "Default")
      (node (ref "P6") (pin "4") (pinfunction "4_4") (pintype "passive"))
      (node (ref "U1") (pin "35") (pinfunction "PB0_35") (pintype "bidirectional"))
    )
    (net (code "22") (name "/PB1") (class "Default")
      (node (ref "P6") (pin "6") (pinfunction "6_6") (pintype "passive"))
      (node (ref "U1") (pin "36") (pinfunction "PB1_36") (pintype "bidirectional"))
    )
    (net (code "23") (name "/PB2") (class "Default")
      (node (ref "P10") (pin "1") (pinfunction "1_1") (pintype "passive"))
      (node (ref "P8") (pin "1") (pinfunction "1_1") (pintype "passive"))
      (node (ref "PB2") (pin "1") (pinfunction "1_1") (pintype "passive"))
      (node (ref "PB2") (pin "2") (pinfunction "2_2") (pintype "passive"))
      (node (ref "U1") (pin "37") (pinfunction "PB2_37") (pintype "bidirectional"))
    )
    (net (code "24") (name "/PB3") (class "Default")
      (node (ref "P1") (pin "8") (pinfunction "8_8") (pintype "passive"))
      (node (ref "P2") (pin "10") (pinfunction "10_10") (pintype "passive"))
      (node (ref "P3") (pin "29") (pinfunction "29_29") (pintype "passive"))
      (node (ref "P5") (pin "4") (pinfunction "4_4") (pintype "passive"))
      (node (ref "U1") (pin "89") (pinfunction "PB3_89") (pintype "bidirectional"))
    )
    (net (code "25") (name "/PB4") (class "Default")
      (node (ref "P1") (pin "9") (pinfunction "9_9") (pintype "passive"))
      (node (ref "P2") (pin "6") (pinfunction "6_6") (pintype "passive"))
      (node (ref "P3") (pin "25") (pinfunction "25_25") (pintype "passive"))
      (node (ref "P5") (pin "1") (pinfunction "1_1") (pintype "passive"))
      (node (ref "R6") (pin "1") (pinfunction "1_1") (pintype "passive"))
      (node (ref "U1") (pin "90") (pinfunction "PB4_90") (pintype "bidirectional"))
    )
    (net (code "26") (name "/PB5") (class "Default")
      (node (ref "P1") (pin "11") (pinfunction "11_11") (pintype "passive"))
      (node (ref "P2") (pin "8") (pinfunction "8_8") (pintype "passive"))
      (node (ref "P3") (pin "27") (pinfunction "27_27") (pintype "passive"))
      (node (ref "U1") (pin "91") (pinfunction "PB5_91") (pintype "bidirectional"))
    )
    (net (code "27") (name "/PB6") (class "Default")
      (node (ref "P2") (pin "15") (pinfunction "15_15") (pintype "passive"))
      (node (ref "U1") (pin "92") (pinfunction "PB6_92") (pintype "bidirectional"))
    )
    (net (code "28") (name "/PB7") (class "Default")
      (node (ref "P2") (pin "13") (pinfunction "13_13") (pintype "passive"))
      (node (ref "U1") (pin "93") (pinfunction "PB7_93") (pintype "bidirectional"))
    )
    (net (code "29") (name "/PB8") (class "Default")
      (node (ref "P2") (pin "2") (pinfunction "2_2") (pintype "passive"))
      (node (ref "U1") (pin "95") (pinfunction "PB8_95") (pintype "bidirectional"))
    )
    (net (code "30") (name "/PB9") (class "Default")
      (node (ref "P2") (pin "4") (pinfunction "4_4") (pintype "passive"))
      (node (ref "U1") (pin "96") (pinfunction "PB9_96") (pintype "bidirectional"))
    )
    (net (code "31") (name "/PB10") (class "Default")
      (node (ref "P3") (pin "28") (pinfunction "28_28") (pintype "passive"))
      (node (ref "U1") (pin "47") (pinfunction "PB10_47") (pintype "bidirectional"))
    )
    (net (code "32") (name "/PB11") (class "Default")
      (node (ref "U1") (pin "48") (pinfunction "PB11_48") (pintype "bidirectional"))
      (node (ref "U4") (pin "16") (pinfunction "TXEN_16") (pintype "input"))
    )
    (net (code "33") (name "/PB12") (class "Default")
      (node (ref "U1") (pin "51") (pinfunction "PB12_51") (pintype "bidirectional"))
      (node (ref "U4") (pin "17") (pinfunction "TXD0_17") (pintype "input"))
    )
    (net (code "34") (name "/PB13") (class "Default")
      (node (ref "U1") (pin "52") (pinfunction "PB13_52") (pintype "bidirectional"))
      (node (ref "U4") (pin "18") (pinfunction "TXD1_18") (pintype "input"))
      (node (ref "W16") (pin "1") (pinfunction "C1_1") (pintype "passive"))
      (node (ref "W9") (pin "1") (pinfunction "C1_1") (pintype "passive"))
    )
    (net (code "35") (name "/PB14") (class "Default")
      (node (ref "P8") (pin "10") (pinfunction "10_10") (pintype "passive"))
      (node (ref "R18") (pin "2") (pinfunction "2_2") (pintype "passive"))
      (node (ref "U1") (pin "53") (pinfunction "PB14_53") (pintype "bidirectional"))
      (node (ref "W15") (pin "1") (pinfunction "C1_1") (pintype "passive"))
      (node (ref "W23") (pin "1") (pinfunction "C1_1") (pintype "passive"))
    )
    (net (code "36") (name "/PB15") (class "Default")
      (node (ref "P8") (pin "12") (pinfunction "12_12") (pintype "passive"))
      (node (ref "R19") (pin "2") (pinfunction "2_2") (pintype "passive"))
      (node (ref "U1") (pin "54") (pinfunction "PB15_54") (pintype "bidirectional"))
      (node (ref "W13") (pin "1") (pinfunction "C1_1") (pintype "passive"))
      (node (ref "W19") (pin "1") (pinfunction "C1_1") (pintype "passive"))
    )
    (net (code "37") (name "/PC0") (class "Default")
      (node (ref "P4") (pin "5") (pinfunction "5_5") (pintype "passive"))
      (node (ref "U1") (pin "15") (pinfunction "PC0_15") (pintype "bidirectional"))
    )
    (net (code "38") (name "/PC1") (class "Default")
      (node (ref "U1") (pin "16") (pinfunction "PC1_16") (pintype "bidirectional"))
      (node (ref "U4") (pin "13") (pinfunction "MDC_13") (pintype "input"))
    )
    (net (code "39") (name "/PC2") (class "Default")
      (node (ref "P4") (pin "6") (pinfunction "6_6") (pintype "passive"))
      (node (ref "U1") (pin "17") (pinfunction "PC2_17") (pintype "bidirectional"))
    )
    (net (code "40") (name "/PC3") (class "Default")
      (node (ref "P4") (pin "7") (pinfunction "7_7") (pintype "passive"))
      (node (ref "U1") (pin "18") (pinfunction "PC3_18") (pintype "bidirectional"))
    )
    (net (code "41") (name "/PC4") (class "Default")
      (node (ref "U1") (pin "33") (pinfunction "PC4_33") (pintype "bidirectional"))
      (node (ref "U4") (pin "8") (pinfunction "RXD0/MODE0_8") (pintype "bidirectional"))
    )
    (net (code "42") (name "/PC5") (class "Default")
      (node (ref "U1") (pin "34") (pinfunction "PC5_34") (pintype "bidirectional"))
      (node (ref "U4") (pin "7") (pinfunction "RXD1/MODE1_7") (pintype "bidirectional"))
    )
    (net (code "43") (name "/PC6") (class "Default")
      (node (ref "P6") (pin "9") (pinfunction "9_9") (pintype "passive"))
      (node (ref "U1") (pin "63") (pinfunction "PC6_63") (pintype "bidirectional"))
    )
    (net (code "44") (name "/PC7") (class "Default")
      (node (ref "P6") (pin "10") (pinfunction "10_10") (pintype "passive"))
      (node (ref "U1") (pin "64") (pinfunction "PC7_64") (pintype "bidirectional"))
    )
    (net (code "45") (name "/PC8") (class "Default")
      (node (ref "P2") (pin "22") (pinfunction "22_22") (pintype "passive"))
      (node (ref "P6") (pin "11") (pinfunction "11_11") (pintype "passive"))
      (node (ref "U1") (pin "65") (pinfunction "PC8_65") (pintype "bidirectional"))
    )
    (net (code "46") (name "/PC9") (class "Default")
      (node (ref "P2") (pin "20") (pinfunction "20_20") (pintype "passive"))
      (node (ref "U1") (pin "66") (pinfunction "PC9_66") (pintype "bidirectional"))
    )
    (net (code "47") (name "/PC10") (class "Default")
      (node (ref "P2") (pin "18") (pinfunction "18_18") (pintype "passive"))
      (node (ref "U1") (pin "78") (pinfunction "PC10_78") (pintype "bidirectional"))
    )
    (net (code "48") (name "/PC11") (class "Default")
      (node (ref "P2") (pin "16") (pinfunction "16_16") (pintype "passive"))
      (node (ref "U1") (pin "79") (pinfunction "PC11_79") (pintype "bidirectional"))
    )
    (net (code "49") (name "/PC12") (class "Default")
      (node (ref "P2") (pin "17") (pinfunction "17_17") (pintype "passive"))
      (node (ref "U1") (pin "80") (pinfunction "PC12_80") (pintype "bidirectional"))
    )
    (net (code "50") (name "/PC13") (class "Default")
      (node (ref "P8") (pin "9") (pinfunction "9_9") (pintype "passive"))
      (node (ref "U1") (pin "7") (pinfunction "PC13-TAMPER-RTC_7") (pintype "bidirectional"))
    )
    (net (code "51") (name "/PC14") (class "Default")
      (node (ref "P8") (pin "11") (pinfunction "11_11") (pintype "passive"))
      (node (ref "U1") (pin "8") (pinfunction "PC14-OSC32_IN_8") (pintype "bidirectional"))
    )
    (net (code "52") (name "/PC15") (class "Default")
      (node (ref "P8") (pin "13") (pinfunction "13_13") (pintype "passive"))
      (node (ref "U1") (pin "9") (pinfunction "PC15-OSC32_OUT_9") (pintype "bidirectional"))
    )
    (net (code "53") (name "/PD0") (class "Default")
      (node (ref "P3") (pin "5") (pinfunction "5_5") (pintype "passive"))
      (node (ref "U1") (pin "81") (pinfunction "PD0_81") (pintype "bidirectional"))
    )
    (net (code "54") (name "/PD1") (class "Default")
      (node (ref "P3") (pin "6") (pinfunction "6_6") (pintype "passive"))
      (node (ref "U1") (pin "82") (pinfunction "PD1_82") (pintype "bidirectional"))
    )
    (net (code "55") (name "/PD2") (class "Default")
      (node (ref "P2") (pin "21") (pinfunction "21_21") (pintype "passive"))
      (node (ref "U1") (pin "83") (pinfunction "PD2_83") (pintype "bidirectional"))
    )
    (net (code "56") (name "/PD3") (class "Default")
      (node (ref "P8") (pin "6") (pinfunction "6_6") (pintype "passive"))
      (node (ref "PB3") (pin "1") (pinfunction "1_1") (pintype "passive"))
      (node (ref "PB3") (pin "2") (pinfunction "2_2") (pintype "passive"))
      (node (ref "U1") (pin "84") (pinfunction "PD3_84") (pintype "bidirectional"))
    )
    (net (code "57") (name "/PD4") (class "Default")
      (node (ref "P3") (pin "22") (pinfunction "22_22") (pintype "passive"))
      (node (ref "U1") (pin "85") (pinfunction "PD4_85") (pintype "bidirectional"))
    )
    (net (code "58") (name "/PD5") (class "Default")
      (node (ref "P3") (pin "21") (pinfunction "21_21") (pintype "passive"))
      (node (ref "U1") (pin "86") (pinfunction "PD5_86") (pintype "bidirectional"))
      (node (ref "W5") (pin "1") (pinfunction "C1_1") (pintype "passive"))
    )
    (net (code "59") (name "/PD6") (class "Default")
      (node (ref "P2") (pin "1") (pinfunction "1_1") (pintype "passive"))
      (node (ref "U1") (pin "87") (pinfunction "PD6_87") (pintype "bidirectional"))
    )
    (net (code "60") (name "/PD7") (class "Default")
      (node (ref "P3") (pin "19") (pinfunction "19_19") (pintype "passive"))
      (node (ref "U1") (pin "88") (pinfunction "PD7_88") (pintype "bidirectional"))
    )
    (net (code "61") (name "/PD8") (class "Default")
      (node (ref "P3") (pin "16") (pinfunction "16_16") (pintype "passive"))
      (node (ref "U1") (pin "55") (pinfunction "PD8_55") (pintype "bidirectional"))
    )
    (net (code "62") (name "/PD9") (class "Default")
      (node (ref "P3") (pin "17") (pinfunction "17_17") (pintype "passive"))
      (node (ref "U1") (pin "56") (pinfunction "PD9_56") (pintype "bidirectional"))
    )
    (net (code "63") (name "/PD10") (class "Default")
      (node (ref "P3") (pin "18") (pinfunction "18_18") (pintype "passive"))
      (node (ref "U1") (pin "57") (pinfunction "PD10_57") (pintype "bidirectional"))
    )
    (net (code "64") (name "/PD11") (class "Default")
      (node (ref "P3") (pin "20") (pinfunction "20_20") (pintype "passive"))
      (node (ref "U1") (pin "58") (pinfunction "PD11_58") (pintype "bidirectional"))
    )
    (net (code "65") (name "/PD12") (class "Default")
      (node (ref "P3") (pin "24") (pinfunction "24_24") (pintype "passive"))
      (node (ref "U1") (pin "59") (pinfunction "PD12_59") (pintype "bidirectional"))
    )
    (net (code "66") (name "/PD13") (class "Default")
      (node (ref "P8") (pin "8") (pinfunction "8_8") (pintype "passive"))
      (node (ref "R15") (pin "1") (pinfunction "1_1") (pintype "passive"))
      (node (ref "U1") (pin "60") (pinfunction "PD13_60") (pintype "bidirectional"))
    )
    (net (code "67") (name "/PD14") (class "Default")
      (node (ref "P3") (pin "3") (pinfunction "3_3") (pintype "passive"))
      (node (ref "U1") (pin "61") (pinfunction "PD14_61") (pintype "bidirectional"))
    )
    (net (code "68") (name "/PD15") (class "Default")
      (node (ref "P3") (pin "4") (pinfunction "4_4") (pintype "passive"))
      (node (ref "U1") (pin "62") (pinfunction "PD15_62") (pintype "bidirectional"))
    )
    (net (code "69") (name "/PE0") (class "Default")
      (node (ref "P2") (pin "12") (pinfunction "12_12") (pintype "passive"))
      (node (ref "U1") (pin "97") (pinfunction "PE0_97") (pintype "bidirectional"))
    )
    (net (code "70") (name "/PE1") (class "Default")
      (node (ref "P2") (pin "14") (pinfunction "14_14") (pintype "passive"))
      (node (ref "U1") (pin "98") (pinfunction "PE1_98") (pintype "bidirectional"))
    )
    (net (code "71") (name "/PE2") (class "Default")
      (node (ref "P3") (pin "23") (pinfunction "23_23") (pintype "passive"))
      (node (ref "U1") (pin "1") (pinfunction "PE2_1") (pintype "bidirectional"))
    )
    (net (code "72") (name "/PE3") (class "Default")
      (node (ref "P3") (pin "31") (pinfunction "31_31") (pintype "passive"))
      (node (ref "U1") (pin "2") (pinfunction "PE3_2") (pintype "bidirectional"))
    )
    (net (code "73") (name "/PE4") (class "Default")
      (node (ref "P3") (pin "26") (pinfunction "26_26") (pintype "passive"))
      (node (ref "U1") (pin "3") (pinfunction "PE4_3") (pintype "bidirectional"))
    )
    (net (code "74") (name "/PE5") (class "Default")
      (node (ref "P3") (pin "30") (pinfunction "30_30") (pintype "passive"))
      (node (ref "U1") (pin "4") (pinfunction "PE5_4") (pintype "bidirectional"))
    )
    (net (code "75") (name "/PE6") (class "Default")
      (node (ref "P3") (pin "32") (pinfunction "32_32") (pintype "passive"))
      (node (ref "U1") (pin "5") (pinfunction "PE6_5") (pintype "bidirectional"))
    )
    (net (code "76") (name "/PE7") (class "Default")
      (node (ref "P3") (pin "7") (pinfunction "7_7") (pintype "passive"))
      (node (ref "U1") (pin "38") (pinfunction "PE7_38") (pintype "bidirectional"))
      (node (ref "W22") (pin "1") (pinfunction "C1_1") (pintype "passive"))
    )
    (net (code "77") (name "/PE8") (class "Default")
      (node (ref "P3") (pin "8") (pinfunction "8_8") (pintype "passive"))
      (node (ref "U1") (pin "39") (pinfunction "PE8_39") (pintype "bidirectional"))
    )
    (net (code "78") (name "/PE9") (class "Default")
      (node (ref "P3") (pin "9") (pinfunction "9_9") (pintype "passive"))
      (node (ref "U1") (pin "40") (pinfunction "PE9_40") (pintype "bidirectional"))
    )
    (net (code "79") (name "/PE10") (class "Default")
      (node (ref "P3") (pin "10") (pinfunction "10_10") (pintype "passive"))
      (node (ref "U1") (pin "41") (pinfunction "PE10_41") (pintype "bidirectional"))
    )
    (net (code "80") (name "/PE11") (class "Default")
      (node (ref "P3") (pin "11") (pinfunction "11_11") (pintype "passive"))
      (node (ref "U1") (pin "42") (pinfunction "PE11_42") (pintype "bidirectional"))
    )
    (net (code "81") (name "/PE12") (class "Default")
      (node (ref "P3") (pin "12") (pinfunction "12_12") (pintype "passive"))
      (node (ref "U1") (pin "43") (pinfunction "PE12_43") (pintype "bidirectional"))
    )
    (net (code "82") (name "/PE13") (class "Default")
      (node (ref "P3") (pin "13") (pinfunction "13_13") (pintype "passive"))
      (node (ref "U1") (pin "44") (pinfunction "PE13_44") (pintype "bidirectional"))
    )
    (net (code "83") (name "/PE14") (class "Default")
      (node (ref "P3") (pin "14") (pinfunction "14_14") (pintype "passive"))
      (node (ref "U1") (pin "45") (pinfunction "PE14_45") (pintype "bidirectional"))
    )
    (net (code "84") (name "/PE15") (class "Default")
      (node (ref "P3") (pin "15") (pinfunction "15_15") (pintype "passive"))
      (node (ref "U1") (pin "46") (pinfunction "PE15_46") (pintype "bidirectional"))
    )
    (net (code "85") (name "/PF6") (class "Default")
      (node (ref "C11") (pin "1") (pinfunction "1_1") (pintype "passive"))
      (node (ref "P8") (pin "15") (pinfunction "15_15") (pintype "passive"))
      (node (ref "U1") (pin "73") (pinfunction "NC_73") (pintype "passive"))
    )
    (net (code "86") (name "/PH0") (class "Default")
      (node (ref "P8") (pin "2") (pinfunction "2_2") (pintype "passive"))
      (node (ref "R10") (pin "2") (pinfunction "2_2") (pintype "passive"))
      (node (ref "U1") (pin "12") (pinfunction "OSC_IN_12") (pintype "input"))
    )
    (net (code "87") (name "/PH1") (class "Default")
      (node (ref "P8") (pin "4") (pinfunction "4_4") (pintype "passive"))
      (node (ref "R20") (pin "2") (pinfunction "2_2") (pintype "passive"))
      (node (ref "U1") (pin "13") (pinfunction "OSC_OUT_13") (pintype "passive"))
    )
    (net (code "88") (name "/RESET") (class "Default")
      (node (ref "C10") (pin "2") (pinfunction "2_2") (pintype "passive"))
      (node (ref "P5") (pin "6") (pinfunction "6_6") (pintype "passive"))
      (node (ref "PB1") (pin "3") (pinfunction "4_3") (pintype "passive"))
      (node (ref "PB1") (pin "4") (pinfunction "4_4") (pintype "passive"))
      (node (ref "R4") (pin "2") (pinfunction "2_2") (pintype "passive"))
      (node (ref "U1") (pin "14") (pinfunction "NRST_14") (pintype "bidirectional"))
      (node (ref "U4") (pin "15") (pinfunction "~{NRST}_15") (pintype "input"))
      (node (ref "W24") (pin "1") (pinfunction "C1_1") (pintype "passive"))
    )
    (net (code "89") (name "/RX+") (class "Default")
      (node (ref "P1") (pin "3") (pinfunction "3_3") (pintype "passive"))
      (node (ref "U4") (pin "23") (pinfunction "RXP_23") (pintype "bidirectional"))
    )
    (net (code "90") (name "/RX-") (class "Default")
      (node (ref "P1") (pin "5") (pinfunction "5_5") (pintype "passive"))
      (node (ref "U4") (pin "22") (pinfunction "RXN_22") (pintype "bidirectional"))
    )
    (net (code "91") (name "/TX+") (class "Default")
      (node (ref "P1") (pin "6") (pinfunction "6_6") (pintype "passive"))
      (node (ref "U4") (pin "21") (pinfunction "TXP_21") (pintype "bidirectional"))
    )
    (net (code "92") (name "/TX-") (class "Default")
      (node (ref "P1") (pin "1") (pinfunction "1_1") (pintype "passive"))
      (node (ref "U4") (pin "20") (pinfunction "TXN_20") (pintype "bidirectional"))
    )
    (net (code "93") (name "3V3") (class "Default")
      (node (ref "C17") (pin "1") (pinfunction "1_1") (pintype "passive"))
      (node (ref "C5") (pin "1") (pinfunction "1_1") (pintype "passive"))
      (node (ref "C7") (pin "1") (pinfunction "1_1") (pintype "passive"))
      (node (ref "JP1") (pin "1") (pinfunction "1_1") (pintype "passive"))
      (node (ref "JP3") (pin "1") (pinfunction "1_1") (pintype "passive"))
      (node (ref "LM1") (pin "1") (pinfunction "1_1") (pintype "passive"))
      (node (ref "LM2") (pin "2") (pinfunction "2_2") (pintype "passive"))
      (node (ref "Osc1") (pin "4") (pinfunction "3.3V_4") (pintype "passive"))
      (node (ref "P2") (pin "19") (pinfunction "19_19") (pintype "passive"))
      (node (ref "P3") (pin "2") (pinfunction "2_2") (pintype "passive"))
      (node (ref "P4") (pin "12") (pinfunction "12_12") (pintype "passive"))
      (node (ref "P6") (pin "12") (pinfunction "12_12") (pintype "passive"))
      (node (ref "P8") (pin "18") (pinfunction "18_18") (pintype "passive"))
      (node (ref "P9") (pin "2") (pinfunction "2_2") (pintype "passive"))
      (node (ref "R12") (pin "2") (pinfunction "2_2") (pintype "passive"))
      (node (ref "R2") (pin "1") (pinfunction "1_1") (pintype "passive"))
      (node (ref "R21") (pin "2") (pinfunction "2_2") (pintype "passive"))
      (node (ref "R4") (pin "1") (pinfunction "1_1") (pintype "passive"))
      (node (ref "R6") (pin "2") (pinfunction "2_2") (pintype "passive"))
      (node (ref "R7") (pin "2") (pinfunction "2_2") (pintype "passive"))
      (node (ref "R8") (pin "2") (pinfunction "2_2") (pintype "passive"))
      (node (ref "R9") (pin "2") (pinfunction "2_2") (pintype "passive"))
      (node (ref "U1") (pin "100") (pinfunction "VDD_3_100") (pintype "power_in"))
      (node (ref "U1") (pin "11") (pinfunction "VDD_5_11") (pintype "power_in"))
      (node (ref "U1") (pin "28") (pinfunction "VDD_4_28") (pintype "power_in"))
      (node (ref "U1") (pin "50") (pinfunction "VDD_1_50") (pintype "power_in"))
      (node (ref "U1") (pin "75") (pinfunction "VDD_2_75") (pintype "power_in"))
      (node (ref "U4") (pin "9") (pinfunction "VDDIO_9") (pintype "power_in"))
      (node (ref "VR1") (pin "4") (pinfunction "Vout_4") (pintype "passive"))
      (node (ref "W1") (pin "2") (pinfunction "C2_2") (pintype "passive"))
    )
    (net (code "94") (name "5V") (class "Default")
      (node (ref "C4") (pin "1") (pinfunction "1_1") (pintype "passive"))
      (node (ref "C6") (pin "1") (pinfunction "1_1") (pintype "passive"))
      (node (ref "P2") (pin "24") (pinfunction "24_24") (pintype "passive"))
      (node (ref "P3") (pin "34") (pinfunction "34_34") (pintype "passive"))
      (node (ref "P4") (pin "14") (pinfunction "14_14") (pintype "passive"))
      (node (ref "P6") (pin "14") (pinfunction "14_14") (pintype "passive"))
      (node (ref "P7") (pin "3") (pinfunction "3_3") (pintype "passive"))
      (node (ref "P8") (pin "20") (pinfunction "20_20") (pintype "passive"))
      (node (ref "POWER1") (pin "1") (pinfunction "1_1") (pintype "passive"))
      (node (ref "Q1") (pin "3") (pinfunction "S_3") (pintype "passive"))
      (node (ref "R13") (pin "2") (pinfunction "2_2") (pintype "passive"))
      (node (ref "R16") (pin "2") (pinfunction "2_2") (pintype "passive"))
      (node (ref "VR1") (pin "3") (pinfunction "Vin_3") (pintype "passive"))
      (node (ref "W10") (pin "2") (pinfunction "C2_2") (pintype "passive"))
      (node (ref "W2") (pin "2") (pinfunction "C2_2") (pintype "passive"))
    )
    (net (code "95") (name "GND") (class "Default")
      (node (ref "BT1") (pin "2") (pinfunction "2_2") (pintype "passive"))
      (node (ref "C1") (pin "1") (pinfunction "1_1") (pintype "passive"))
      (node (ref "C10") (pin "1") (pinfunction "1_1") (pintype "passive"))
      (node (ref "C11") (pin "2") (pinfunction "2_2") (pintype "passive"))
      (node (ref "C12") (pin "2") (pinfunction "2_2") (pintype "passive"))
      (node (ref "C13") (pin "1") (pinfunction "1_1") (pintype "passive"))
      (node (ref "C14") (pin "2") (pinfunction "2_2") (pintype "passive"))
      (node (ref "C15") (pin "2") (pinfunction "2_2") (pintype "passive"))
      (node (ref "C16") (pin "1") (pinfunction "1_1") (pintype "passive"))
      (node (ref "C17") (pin "2") (pinfunction "2_2") (pintype "passive"))
      (node (ref "C18") (pin "1") (pinfunction "1_1") (pintype "passive"))
      (node (ref "C2") (pin "1") (pinfunction "1_1") (pintype "passive"))
      (node (ref "C3") (pin "2") (pinfunction "2_2") (pintype "passive"))
      (node (ref "C4") (pin "2") (pinfunction "2_2") (pintype "passive"))
      (node (ref "C5") (pin "2") (pinfunction "2_2") (pintype "passive"))
      (node (ref "C6") (pin "2") (pinfunction "2_2") (pintype "passive"))
      (node (ref "C7") (pin "2") (pinfunction "2_2") (pintype "passive"))
      (node (ref "C8") (pin "1") (pinfunction "1_1") (pintype "passive"))
      (node (ref "C9") (pin "1") (pinfunction "1_1") (pintype "passive"))
      (node (ref "D1") (pin "2") (pinfunction "K_2") (pintype "passive"))
      (node (ref "D3") (pin "2") (pinfunction "K_2") (pintype "passive"))
      (node (ref "D4") (pin "2") (pinfunction "K_2") (pintype "passive"))
      (node (ref "D5") (pin "2") (pinfunction "K_2") (pintype "passive"))
      (node (ref "J1") (pin "4") (pinfunction "GND_4") (pintype "power_in"))
      (node (ref "J1") (pin "5") (pinfunction "GND_5") (pintype "passive"))
      (node (ref "J1") (pin "6") (pinfunction "GND_6") (pintype "passive"))
      (node (ref "J2") (pin "4") (pinfunction "GND_4") (pintype "power_in"))
      (node (ref "J2") (pin "5") (pinfunction "SHLD_5") (pintype "passive"))
      (node (ref "J2") (pin "6") (pinfunction "SHLD_6") (pintype "passive"))
      (node (ref "JP2") (pin "1") (pinfunction "1_1") (pintype "passive"))
      (node (ref "JP3") (pin "3") (pinfunction "3_3") (pintype "passive"))
      (node (ref "Osc1") (pin "2") (pinfunction "GND_2") (pintype "passive"))
      (node (ref "P1") (pin "12") (pinfunction "12_12") (pintype "passive"))
      (node (ref "P10") (pin "2") (pinfunction "2_2") (pintype "passive"))
      (node (ref "P2") (pin "23") (pinfunction "23_23") (pintype "passive"))
      (node (ref "P3") (pin "1") (pinfunction "1_1") (pintype "passive"))
      (node (ref "P3") (pin "33") (pinfunction "33_33") (pintype "passive"))
      (node (ref "P4") (pin "11") (pinfunction "11_11") (pintype "passive"))
      (node (ref "P4") (pin "13") (pinfunction "13_13") (pintype "passive"))
      (node (ref "P5") (pin "2") (pinfunction "2_2") (pintype "passive"))
      (node (ref "P5") (pin "8") (pinfunction "8_8") (pintype "passive"))
      (node (ref "P6") (pin "13") (pinfunction "13_13") (pintype "passive"))
      (node (ref "P7") (pin "4") (pinfunction "4_4") (pintype "passive"))
      (node (ref "P8") (pin "19") (pinfunction "19_19") (pintype "passive"))
      (node (ref "PB1") (pin "1") (pinfunction "1_1") (pintype "passive"))
      (node (ref "PB1") (pin "2") (pinfunction "2_2") (pintype "passive"))
      (node (ref "PB2") (pin "3") (pinfunction "4_3") (pintype "passive"))
      (node (ref "PB2") (pin "4") (pinfunction "4_4") (pintype "passive"))
      (node (ref "PB3") (pin "3") (pinfunction "4_3") (pintype "passive"))
      (node (ref "PB3") (pin "4") (pinfunction "4_4") (pintype "passive"))
      (node (ref "POWER1") (pin "2") (pinfunction "2_2") (pintype "passive"))
      (node (ref "Q2") (pin "2") (pinfunction "E_2") (pintype "passive"))
      (node (ref "R17") (pin "2") (pinfunction "2_2") (pintype "passive"))
      (node (ref "R22") (pin "2") (pinfunction "2_2") (pintype "passive"))
      (node (ref "R5") (pin "2") (pinfunction "2_2") (pintype "passive"))
      (node (ref "U1") (pin "10") (pinfunction "VSS_5_10") (pintype "power_in"))
      (node (ref "U1") (pin "27") (pinfunction "VSS_4_27") (pintype "power_in"))
      (node (ref "U1") (pin "74") (pinfunction "VSS_2_74") (pintype "power_in"))
      (node (ref "U1") (pin "99") (pinfunction "VSS_3_99") (pintype "power_in"))
      (node (ref "U2") (pin "2") (pinfunction "GND_2") (pintype "passive"))
      (node (ref "U3") (pin "2") (pinfunction "GND_2") (pintype "passive"))
      (node (ref "U4") (pin "25") (pinfunction "VSS_25") (pintype "power_in"))
      (node (ref "VR1") (pin "1") (pinfunction "GND_1") (pintype "passive"))
      (node (ref "W3") (pin "2") (pinfunction "C2_2") (pintype "passive"))
    )
    (net (code "96") (name "Net-(BT1-Pad1)") (class "Default")
      (node (ref "BT1") (pin "1") (pinfunction "1_1") (pintype "passive"))
      (node (ref "JP1") (pin "3") (pinfunction "3_3") (pintype "passive"))
    )
    (net (code "97") (name "Net-(C3-Pad1)") (class "Default")
      (node (ref "C3") (pin "1") (pinfunction "1_1") (pintype "passive"))
      (node (ref "JP2") (pin "3") (pinfunction "3_3") (pintype "passive"))
    )
    (net (code "98") (name "Net-(C14-Pad1)") (class "Default")
      (node (ref "C14") (pin "1") (pinfunction "1_1") (pintype "passive"))
      (node (ref "R10") (pin "1") (pinfunction "1_1") (pintype "passive"))
      (node (ref "X1") (pin "1") (pinfunction "1_1") (pintype "passive"))
    )
    (net (code "99") (name "Net-(C15-Pad1)") (class "Default")
      (node (ref "C15") (pin "1") (pinfunction "1_1") (pintype "passive"))
      (node (ref "R20") (pin "1") (pinfunction "1_1") (pintype "passive"))
      (node (ref "X1") (pin "2") (pinfunction "2_2") (pintype "passive"))
    )
    (net (code "100") (name "Net-(D1-A)") (class "Default")
      (node (ref "D1") (pin "1") (pinfunction "A_1") (pintype "passive"))
      (node (ref "R2") (pin "2") (pinfunction "2_2") (pintype "passive"))
    )
    (net (code "101") (name "Net-(D3-A)") (class "Default")
      (node (ref "D3") (pin "1") (pinfunction "A_1") (pintype "passive"))
      (node (ref "R11") (pin "1") (pinfunction "1_1") (pintype "passive"))
    )
    (net (code "102") (name "Net-(D4-A)") (class "Default")
      (node (ref "D4") (pin "1") (pinfunction "A_1") (pintype "passive"))
      (node (ref "R18") (pin "1") (pinfunction "1_1") (pintype "passive"))
    )
    (net (code "103") (name "Net-(D5-A)") (class "Default")
      (node (ref "D5") (pin "1") (pinfunction "A_1") (pintype "passive"))
      (node (ref "R19") (pin "1") (pinfunction "1_1") (pintype "passive"))
    )
    (net (code "104") (name "Net-(J1-D+)") (class "Default")
      (node (ref "J1") (pin "3") (pinfunction "D+_3") (pintype "input"))
      (node (ref "U2") (pin "4") (pinfunction "I/O2_4") (pintype "passive"))
    )
    (net (code "105") (name "Net-(J1-D-)") (class "Default")
      (node (ref "J1") (pin "2") (pinfunction "D-_2") (pintype "input"))
      (node (ref "U2") (pin "6") (pinfunction "I/O1_6") (pintype "passive"))
    )
    (net (code "106") (name "Net-(J1-VBUS)") (class "Default")
      (node (ref "D2") (pin "A") (pinfunction "A_A") (pintype "passive"))
      (node (ref "J1") (pin "1") (pinfunction "VBUS_1") (pintype "power_in"))
      (node (ref "R3") (pin "2") (pinfunction "2_2") (pintype "passive"))
      (node (ref "U2") (pin "5") (pinfunction "VBUS_5") (pintype "passive"))
    )
    (net (code "107") (name "Net-(J2-D+)") (class "Default")
      (node (ref "J2") (pin "3") (pinfunction "D+_3") (pintype "input"))
      (node (ref "U3") (pin "4") (pinfunction "I/O2_4") (pintype "passive"))
    )
    (net (code "108") (name "Net-(J2-D-)") (class "Default")
      (node (ref "J2") (pin "2") (pinfunction "D-_2") (pintype "input"))
      (node (ref "U3") (pin "6") (pinfunction "I/O1_6") (pintype "passive"))
    )
    (net (code "109") (name "Net-(J2-VBUS)") (class "Default")
      (node (ref "C12") (pin "1") (pinfunction "1_1") (pintype "passive"))
      (node (ref "C13") (pin "2") (pinfunction "2_2") (pintype "passive"))
      (node (ref "J2") (pin "1") (pinfunction "VBUS_1") (pintype "power_in"))
      (node (ref "Q1") (pin "1") (pinfunction "D_1") (pintype "passive"))
      (node (ref "R11") (pin "2") (pinfunction "2_2") (pintype "passive"))
      (node (ref "U3") (pin "5") (pinfunction "VBUS_5") (pintype "passive"))
      (node (ref "W16") (pin "2") (pinfunction "C2_2") (pintype "passive"))
      (node (ref "W17") (pin "2") (pinfunction "C2_2") (pintype "passive"))
    )
    (net (code "110") (name "Net-(Osc1-INH)") (class "Default")
      (node (ref "Osc1") (pin "1") (pinfunction "INH_1") (pintype "passive"))
      (node (ref "R21") (pin "1") (pinfunction "1_1") (pintype "passive"))
    )
    (net (code "111") (name "Net-(P5-Pad9)") (class "Default")
      (node (ref "P5") (pin "9") (pinfunction "9_9") (pintype "passive"))
      (node (ref "R12") (pin "1") (pinfunction "1_1") (pintype "passive"))
    )
    (net (code "112") (name "Net-(P5-Pad10)") (class "Default")
      (node (ref "P5") (pin "10") (pinfunction "10_10") (pintype "passive"))
      (node (ref "R13") (pin "1") (pinfunction "1_1") (pintype "passive"))
    )
    (net (code "113") (name "Net-(Q1-G)") (class "Default")
      (node (ref "Q1") (pin "2") (pinfunction "G_2") (pintype "passive"))
      (node (ref "R14") (pin "1") (pinfunction "1_1") (pintype "passive"))
    )
    (net (code "114") (name "Net-(Q2-B)") (class "Default")
      (node (ref "Q2") (pin "1") (pinfunction "B_1") (pintype "passive"))
      (node (ref "R15") (pin "2") (pinfunction "2_2") (pintype "passive"))
    )
    (net (code "115") (name "Net-(Q2-C)") (class "Default")
      (node (ref "Q2") (pin "3") (pinfunction "C_3") (pintype "passive"))
      (node (ref "R14") (pin "2") (pinfunction "2_2") (pintype "passive"))
      (node (ref "R16") (pin "1") (pinfunction "1_1") (pintype "passive"))
    )
    (net (code "116") (name "Net-(U1B-VBAT)") (class "Default")
      (node (ref "JP1") (pin "2") (pinfunction "2_2") (pintype "passive"))
      (node (ref "U1") (pin "6") (pinfunction "VBAT_6") (pintype "power_in"))
    )
    (net (code "117") (name "Net-(U1B-VSS_1)") (class "Default")
      (node (ref "JP2") (pin "2") (pinfunction "2_2") (pintype "passive"))
      (node (ref "U1") (pin "49") (pinfunction "VSS_1_49") (pintype "power_in"))
    )
    (net (code "118") (name "Net-(U4-MDIO)") (class "Default")
      (node (ref "R23") (pin "1") (pinfunction "1_1") (pintype "passive"))
      (node (ref "U4") (pin "12") (pinfunction "MDIO_12") (pintype "bidirectional"))
    )
    (net (code "119") (name "Net-(U4-RBIAS)") (class "Default")
      (node (ref "R22") (pin "1") (pinfunction "1_1") (pintype "passive"))
      (node (ref "U4") (pin "24") (pinfunction "RBIAS_24") (pintype "input"))
    )
    (net (code "120") (name "Net-(U4-VDD1A)") (class "Default")
      (node (ref "LM2") (pin "1") (pinfunction "1_1") (pintype "passive"))
      (node (ref "U4") (pin "1") (pinfunction "VDD2A_1") (pintype "power_in"))
      (node (ref "U4") (pin "19") (pinfunction "VDD1A_19") (pintype "power_in"))
    )
    (net (code "121") (name "Net-(U4-VDDCR)") (class "Default")
      (node (ref "C16") (pin "2") (pinfunction "2_2") (pintype "passive"))
      (node (ref "C18") (pin "2") (pinfunction "2_2") (pintype "passive"))
      (node (ref "U4") (pin "6") (pinfunction "VDDCR_6") (pintype "power_in"))
    )
    (net (code "122") (name "Net-(W1-C1)") (class "Default")
      (node (ref "P1") (pin "10") (pinfunction "10_10") (pintype "passive"))
      (node (ref "W1") (pin "1") (pinfunction "C1_1") (pintype "passive"))
      (node (ref "W2") (pin "1") (pinfunction "C1_1") (pintype "passive"))
    )
    (net (code "123") (name "Net-(W5-C2)") (class "Default")
      (node (ref "P2") (pin "3") (pinfunction "3_3") (pintype "passive"))
      (node (ref "W5") (pin "2") (pinfunction "C2_2") (pintype "passive"))
    )
    (net (code "124") (name "Net-(W7-C2)") (class "Default")
      (node (ref "P2") (pin "9") (pinfunction "9_9") (pintype "passive"))
      (node (ref "W7") (pin "2") (pinfunction "C2_2") (pintype "passive"))
    )
    (net (code "125") (name "Net-(W8-C2)") (class "Default")
      (node (ref "P2") (pin "11") (pinfunction "11_11") (pintype "passive"))
      (node (ref "W8") (pin "2") (pinfunction "C2_2") (pintype "passive"))
    )
    (net (code "126") (name "Net-(W10-C1)") (class "Default")
      (node (ref "D2") (pin "K") (pinfunction "K_K") (pintype "passive"))
      (node (ref "W10") (pin "1") (pinfunction "C1_1") (pintype "passive"))
    )
    (net (code "127") (name "Net-(W11-C2)") (class "Default")
      (node (ref "U2") (pin "1") (pinfunction "I/O1_1") (pintype "passive"))
      (node (ref "W11") (pin "2") (pinfunction "C2_2") (pintype "passive"))
      (node (ref "W13") (pin "2") (pinfunction "C2_2") (pintype "passive"))
    )
    (net (code "128") (name "Net-(W12-C2)") (class "Default")
      (node (ref "R3") (pin "1") (pinfunction "1_1") (pintype "passive"))
      (node (ref "R5") (pin "1") (pinfunction "1_1") (pintype "passive"))
      (node (ref "W12") (pin "2") (pinfunction "C2_2") (pintype "passive"))
      (node (ref "W9") (pin "2") (pinfunction "C2_2") (pintype "passive"))
    )
    (net (code "129") (name "Net-(W14-C2)") (class "Default")
      (node (ref "U2") (pin "3") (pinfunction "I/O2_3") (pintype "passive"))
      (node (ref "W14") (pin "2") (pinfunction "C2_2") (pintype "passive"))
      (node (ref "W15") (pin "2") (pinfunction "C2_2") (pintype "passive"))
    )
    (net (code "130") (name "Net-(W18-C2)") (class "Default")
      (node (ref "U3") (pin "1") (pinfunction "I/O1_1") (pintype "passive"))
      (node (ref "W18") (pin "2") (pinfunction "C2_2") (pintype "passive"))
      (node (ref "W19") (pin "2") (pinfunction "C2_2") (pintype "passive"))
    )
    (net (code "131") (name "Net-(W20-C2)") (class "Default")
      (node (ref "P6") (pin "7") (pinfunction "7_7") (pintype "passive"))
      (node (ref "W20") (pin "2") (pinfunction "C2_2") (pintype "passive"))
      (node (ref "W22") (pin "2") (pinfunction "C2_2") (pintype "passive"))
    )
    (net (code "132") (name "Net-(W21-C2)") (class "Default")
      (node (ref "U3") (pin "3") (pinfunction "I/O2_3") (pintype "passive"))
      (node (ref "W21") (pin "2") (pinfunction "C2_2") (pintype "passive"))
      (node (ref "W23") (pin "2") (pinfunction "C2_2") (pintype "passive"))
    )
    (net (code "133") (name "Net-(W24-C2)") (class "Default")
      (node (ref "P8") (pin "17") (pinfunction "17_17") (pintype "passive"))
      (node (ref "W24") (pin "2") (pinfunction "C2_2") (pintype "passive"))
    )
    (net (code "134") (name "VDDA") (class "Default")
      (node (ref "C8") (pin "2") (pinfunction "2_2") (pintype "passive"))
      (node (ref "C9") (pin "2") (pinfunction "2_2") (pintype "passive"))
      (node (ref "LM1") (pin "2") (pinfunction "2_2") (pintype "passive"))
      (node (ref "R1") (pin "2") (pinfunction "2_2") (pintype "passive"))
      (node (ref "W6") (pin "1") (pinfunction "C1_1") (pintype "passive"))
    )
    (net (code "135") (name "VDDAO") (class "Default")
      (node (ref "P8") (pin "16") (pinfunction "16_16") (pintype "passive"))
      (node (ref "U1") (pin "22") (pinfunction "VDDA_22") (pintype "power_in"))
      (node (ref "W6") (pin "2") (pinfunction "C2_2") (pintype "passive"))
    )
    (net (code "136") (name "VREF+") (class "Default")
      (node (ref "P4") (pin "4") (pinfunction "4_4") (pintype "passive"))
      (node (ref "U1") (pin "21") (pinfunction "VREF+_21") (pintype "power_in"))
      (node (ref "W4") (pin "1") (pinfunction "C1_1") (pintype "passive"))
    )
    (net (code "137") (name "VREF++") (class "Default")
      (node (ref "C1") (pin "2") (pinfunction "2_2") (pintype "passive"))
      (node (ref "C2") (pin "2") (pinfunction "2_2") (pintype "passive"))
      (node (ref "R1") (pin "1") (pinfunction "1_1") (pintype "passive"))
      (node (ref "W4") (pin "2") (pinfunction "C2_2") (pintype "passive"))
    )
    (net (code "138") (name "VREF-") (class "Default")
      (node (ref "P4") (pin "3") (pinfunction "3_3") (pintype "passive"))
      (node (ref "U1") (pin "20") (pinfunction "VREF-_20") (pintype "power_in"))
      (node (ref "W3") (pin "1") (pinfunction "C1_1") (pintype "passive"))
    )
    (net (code "139") (name "VSSAO") (class "Default")
      (node (ref "JP3") (pin "2") (pinfunction "2_2") (pintype "passive"))
      (node (ref "P8") (pin "14") (pinfunction "14_14") (pintype "passive"))
      (node (ref "U1") (pin "19") (pinfunction "VSSA_19") (pintype "power_in"))
    )
    (net (code "140") (name "unconnected-(M1-PadS)") (class "Default")
      (node (ref "M1") (pin "S") (pinfunction "S_S") (pintype "passive"))
    )
    (net (code "141") (name "unconnected-(M2-PadS)") (class "Default")
      (node (ref "M2") (pin "S") (pinfunction "S_S") (pintype "passive"))
    )
    (net (code "142") (name "unconnected-(M3-PadS)") (class "Default")
      (node (ref "M3") (pin "S") (pinfunction "S_S") (pintype "passive"))
    )
    (net (code "143") (name "unconnected-(M4-PadS)") (class "Default")
      (node (ref "M4") (pin "S") (pinfunction "S_S") (pintype "passive"))
    )
    (net (code "144") (name "unconnected-(P1-Pad7)") (class "Default")
      (node (ref "P1") (pin "7") (pinfunction "7_7") (pintype "passive"))
    )
    (net (code "145") (name "unconnected-(P4-Pad10)") (class "Default")
      (node (ref "P4") (pin "10") (pinfunction "10_10") (pintype "passive"))
    )
    (net (code "146") (name "unconnected-(U4-RXER{slash}PHYADO-Pad10)") (class "Default")
      (node (ref "U4") (pin "10") (pinfunction "RXER/PHYADO_10") (pintype "bidirectional+no_connect"))
    )
    (net (code "147") (name "unconnected-(U4-XTAL2-Pad4)") (class "Default")
      (node (ref "U4") (pin "4") (pinfunction "XTAL2_4") (pintype "output+no_connect"))
    )
  )
)
